# Custom_Arduino.net
KiCad netlist of a schematic drawn in Altium Designer
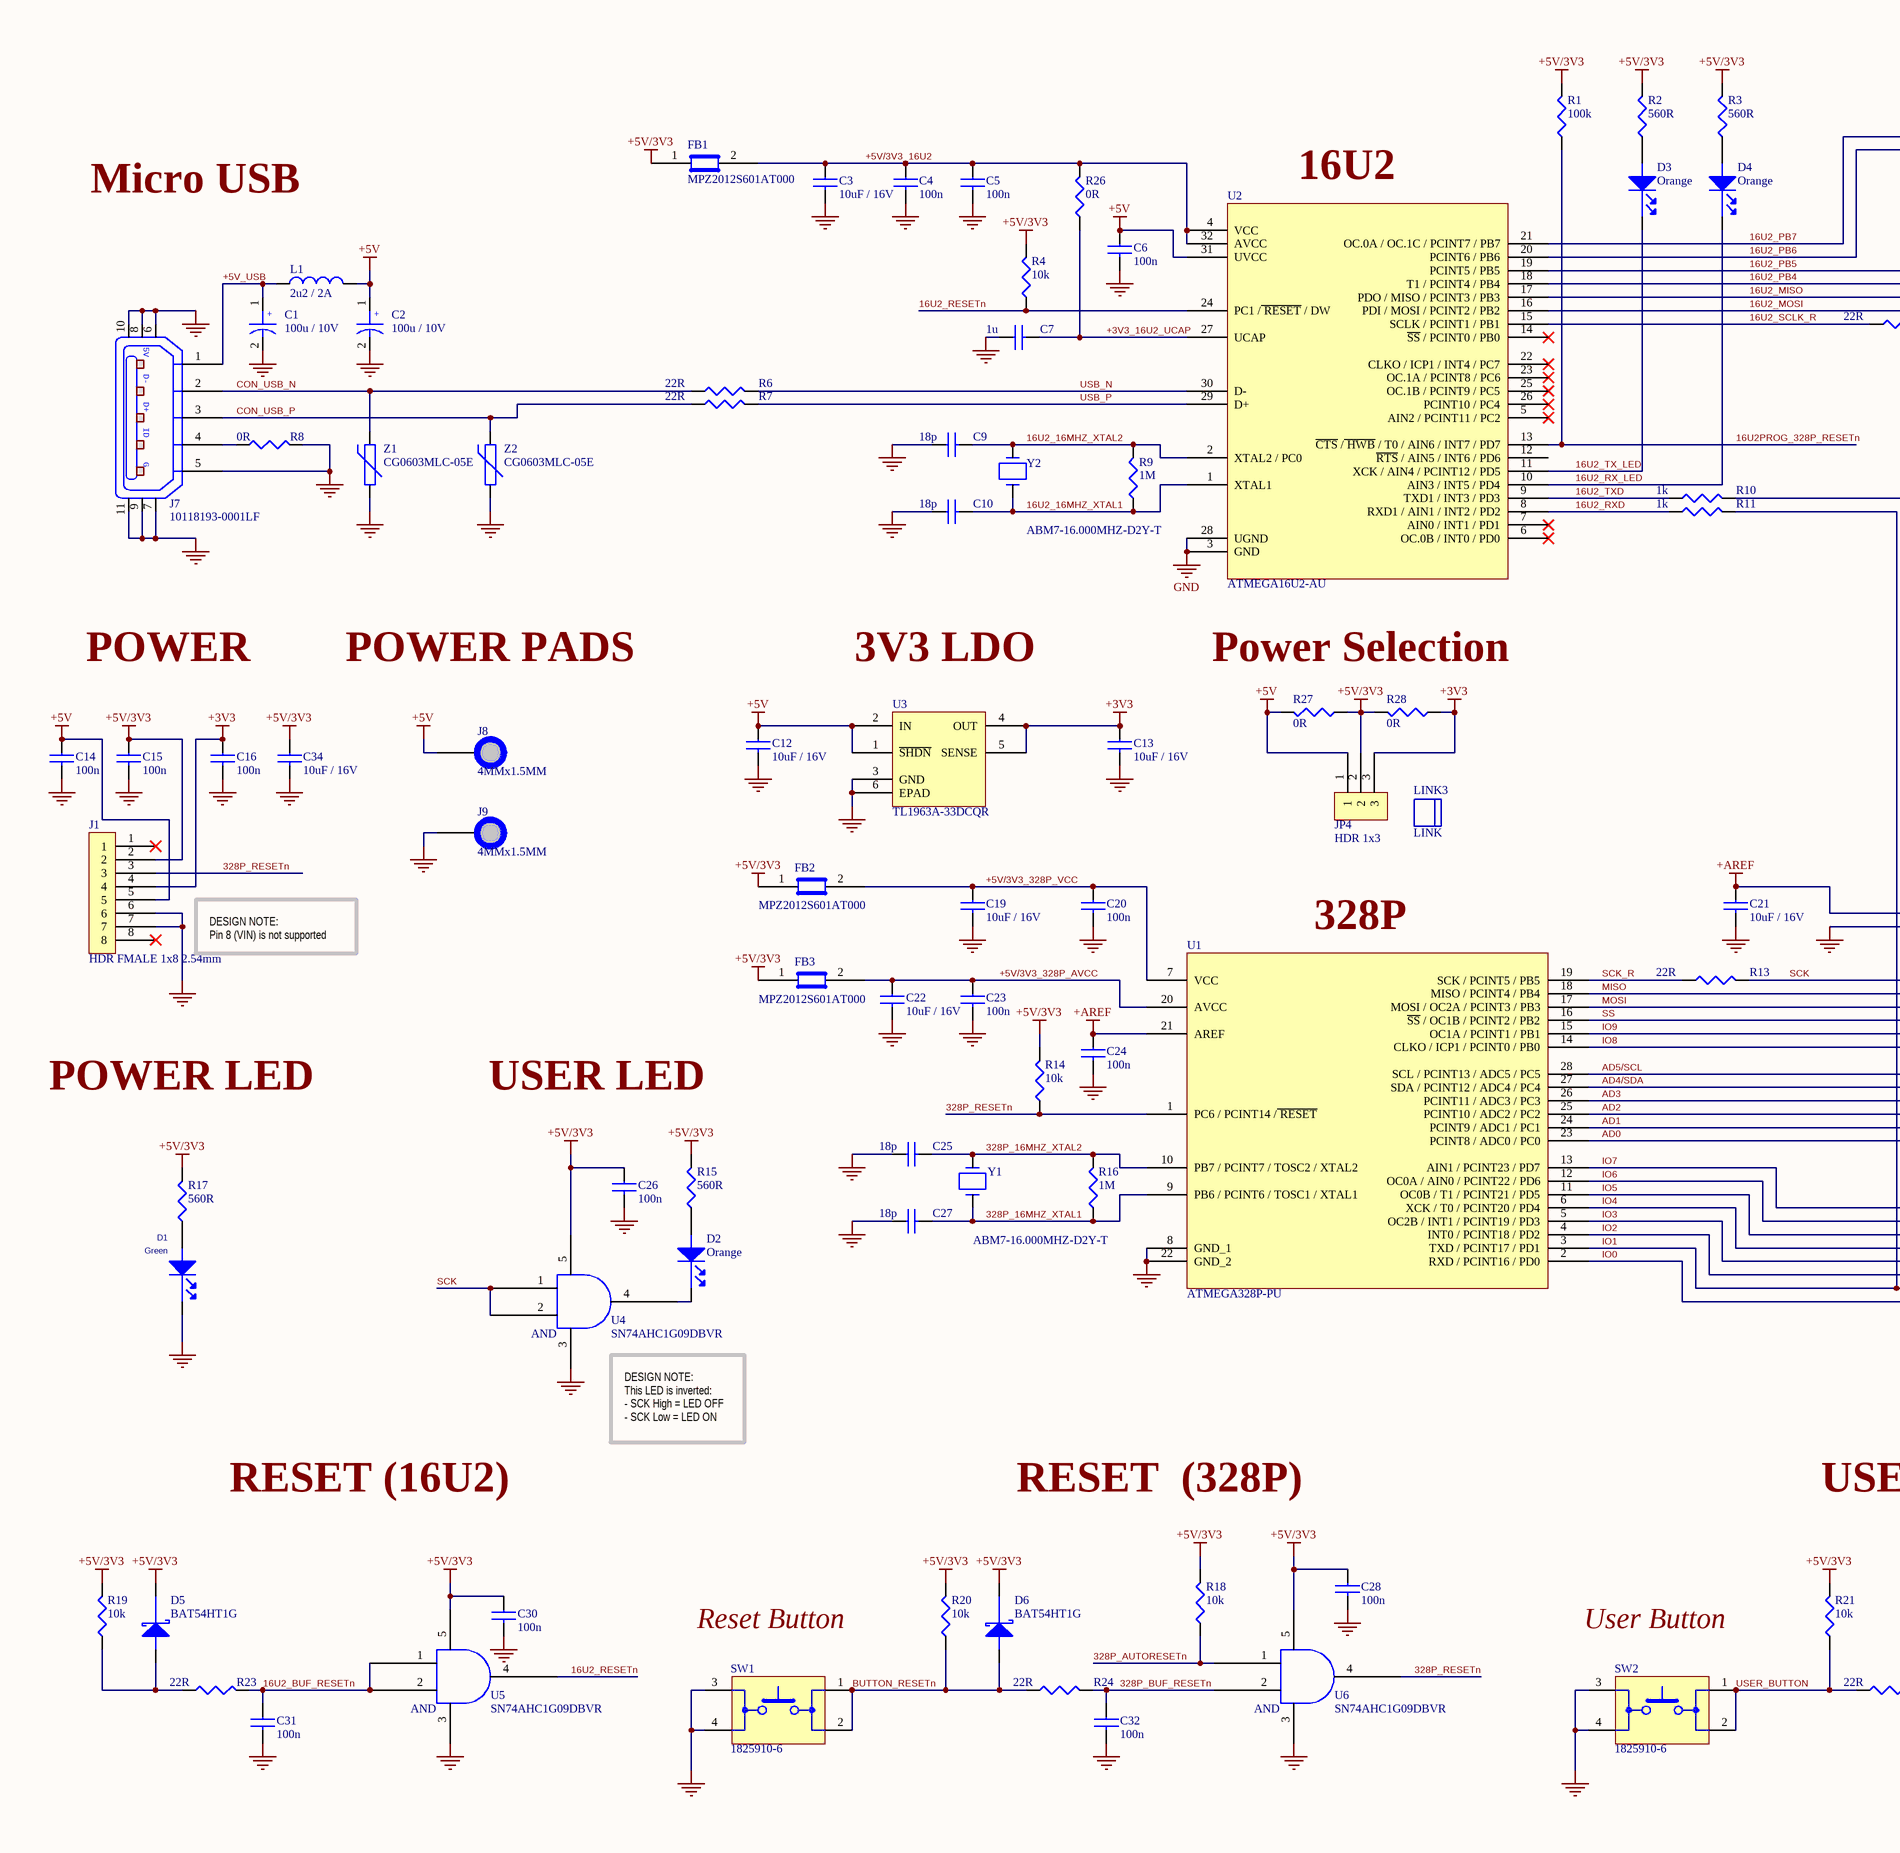
[diagram p0: Custom_Arduino.SchDoc, left]
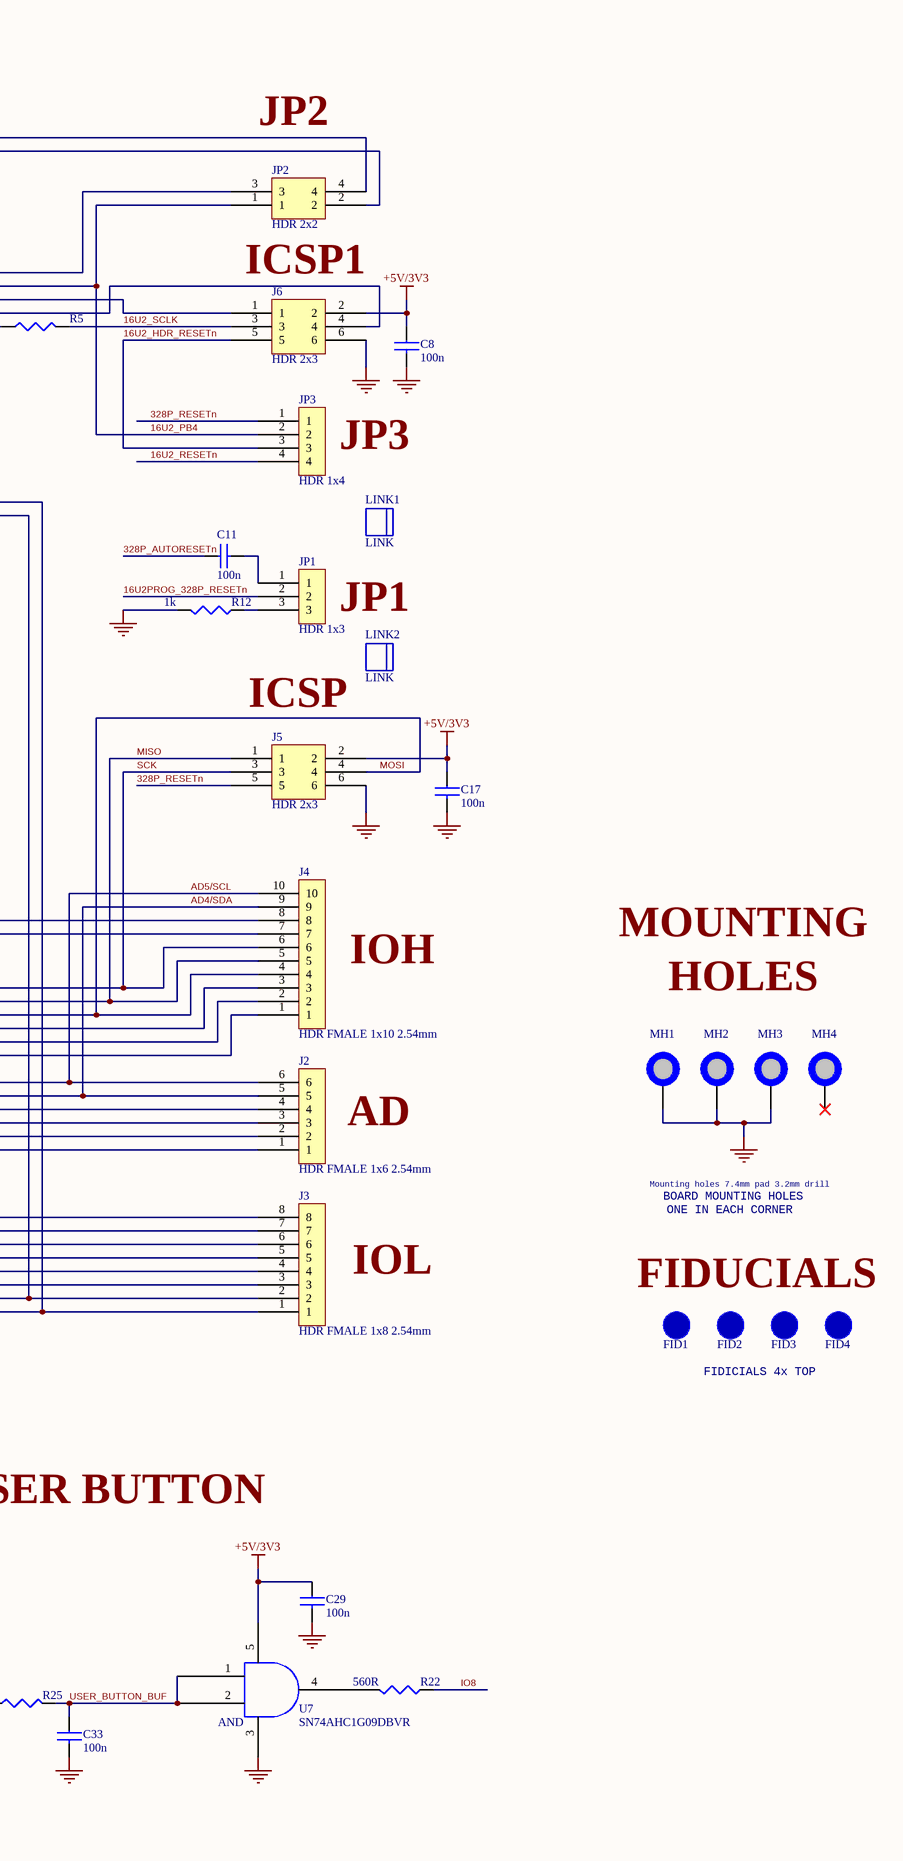
[diagram p1: Custom_Arduino.SchDoc, right]

(export (version "E")
  (design (tool "Eeschema 10.0.6"))
  (components
    (comp (ref "C1")
      (value "100u / 10V")
      (footprint "C_ALU_C_SIZE")
      (description "CAP ALUM 100UF 10V 20% SMD")
      (fields
        (field (name "MANUFACTURER") "Panasonic Electronic Components")
        (field (name "MANUFACTURER PART NUMBER") "EEE-1AA101WR")
        (field (name ".CREATOR") "MM")
        (field (name ".CHECKED PCB") "RF")
        (field (name ".CHECKED SCH") "RF")
      )
      (libsource (lib "My_lib") (part "EEE-1AA101WR"))
    )
    (comp (ref "C2")
      (value "100u / 10V")
      (footprint "C_ALU_C_SIZE")
      (description "CAP ALUM 100UF 10V 20% SMD")
      (fields
        (field (name "MANUFACTURER") "Panasonic Electronic Components")
        (field (name "MANUFACTURER PART NUMBER") "EEE-1AA101WR")
        (field (name ".CREATOR") "MM")
        (field (name ".CHECKED PCB") "RF")
        (field (name ".CHECKED SCH") "RF")
      )
      (libsource (lib "My_lib") (part "EEE-1AA101WR"))
    )
    (comp (ref "C3")
      (value "10uF / 16V")
      (footprint "C0805")
      (description "CAP CER 10UF 16V 20% X5R 0805")
      (fields
        (field (name "MANUFACTURER") "TDK Corporation")
        (field (name "MANUFACTURER PART NUMBER") "C2012X5R1C106M/1.25")
      )
      (libsource (lib "My_lib") (part "C2012X5R1C106M"))
    )
    (comp (ref "C4")
      (value "100n")
      (footprint "C0805")
      (description "CAP CER 0.1UF 50V 10% X7R 0805")
      (fields
        (field (name "MANUFACTURER") "TDK Corporation")
        (field (name "MANUFACTURER PART NUMBER") "C2012X7R1H104K085AA")
        (field (name ".CREATOR") "MM")
        (field (name ".CHECKED PCB") "RF")
        (field (name ".CHECKED SCH") "RF")
      )
      (libsource (lib "My_lib") (part "C2012X7R1H104K085AA"))
    )
    (comp (ref "C5")
      (value "100n")
      (footprint "C0805")
      (description "CAP CER 0.1UF 50V 10% X7R 0805")
      (fields
        (field (name "MANUFACTURER") "TDK Corporation")
        (field (name "MANUFACTURER PART NUMBER") "C2012X7R1H104K085AA")
        (field (name ".CREATOR") "MM")
        (field (name ".CHECKED PCB") "RF")
        (field (name ".CHECKED SCH") "RF")
      )
      (libsource (lib "My_lib") (part "C2012X7R1H104K085AA"))
    )
    (comp (ref "C6")
      (value "100n")
      (footprint "C0805")
      (description "CAP CER 0.1UF 50V 10% X7R 0805")
      (fields
        (field (name "MANUFACTURER") "TDK Corporation")
        (field (name "MANUFACTURER PART NUMBER") "C2012X7R1H104K085AA")
        (field (name ".CREATOR") "MM")
        (field (name ".CHECKED PCB") "RF")
        (field (name ".CHECKED SCH") "RF")
      )
      (libsource (lib "My_lib") (part "C2012X7R1H104K085AA"))
    )
    (comp (ref "C7")
      (value "1u")
      (footprint "C0805")
      (description "CAP CER 1UF 25V 10% X5R 0805")
      (fields
        (field (name "MANUFACTURER") "TDK Corporation")
        (field (name "MANUFACTURER PART NUMBER") "C2012X5R1E105K125AA")
        (field (name ".CREATOR") "MM")
        (field (name ".CHECKED PCB") "RF")
        (field (name ".CHECKED SCH") "RF")
      )
      (libsource (lib "My_lib") (part "C2012X5R1E105K125AA"))
    )
    (comp (ref "C8")
      (value "100n")
      (footprint "C0805")
      (description "CAP CER 0.1UF 50V 10% X7R 0805")
      (fields
        (field (name "MANUFACTURER") "TDK Corporation")
        (field (name "MANUFACTURER PART NUMBER") "C2012X7R1H104K085AA")
        (field (name ".CREATOR") "MM")
        (field (name ".CHECKED PCB") "RF")
        (field (name ".CHECKED SCH") "RF")
      )
      (libsource (lib "My_lib") (part "C2012X7R1H104K085AA"))
    )
    (comp (ref "C9")
      (value "18p")
      (footprint "C0805")
      (description "CAP CER 18PF 50V 5% NP0 0805")
      (fields
        (field (name "MANUFACTURER") "Kemet")
        (field (name "MANUFACTURER PART NUMBER") "C0805C180J5GACTU")
        (field (name ".CREATOR") "MM")
        (field (name ".CHECKED PCB") "RF")
        (field (name ".CHECKED SCH") "RF")
      )
      (libsource (lib "My_lib") (part "C0805C180J5GACTU"))
    )
    (comp (ref "C10")
      (value "18p")
      (footprint "C0805")
      (description "CAP CER 18PF 50V 5% NP0 0805")
      (fields
        (field (name "MANUFACTURER") "Kemet")
        (field (name "MANUFACTURER PART NUMBER") "C0805C180J5GACTU")
        (field (name ".CREATOR") "MM")
        (field (name ".CHECKED PCB") "RF")
        (field (name ".CHECKED SCH") "RF")
      )
      (libsource (lib "My_lib") (part "C0805C180J5GACTU"))
    )
    (comp (ref "C11")
      (value "100n")
      (footprint "C0805")
      (description "CAP CER 0.1UF 50V 10% X7R 0805")
      (fields
        (field (name "MANUFACTURER") "TDK Corporation")
        (field (name "MANUFACTURER PART NUMBER") "C2012X7R1H104K085AA")
        (field (name ".CREATOR") "MM")
        (field (name ".CHECKED PCB") "RF")
        (field (name ".CHECKED SCH") "RF")
      )
      (libsource (lib "My_lib") (part "C2012X7R1H104K085AA"))
    )
    (comp (ref "C12")
      (value "10uF / 16V")
      (footprint "C0805")
      (description "CAP CER 10UF 16V 20% X5R 0805")
      (fields
        (field (name "MANUFACTURER") "TDK Corporation")
        (field (name "MANUFACTURER PART NUMBER") "C2012X5R1C106M/1.25")
      )
      (libsource (lib "My_lib") (part "C2012X5R1C106M"))
    )
    (comp (ref "C13")
      (value "10uF / 16V")
      (footprint "C0805")
      (description "CAP CER 10UF 16V 20% X5R 0805")
      (fields
        (field (name "MANUFACTURER") "TDK Corporation")
        (field (name "MANUFACTURER PART NUMBER") "C2012X5R1C106M/1.25")
      )
      (libsource (lib "My_lib") (part "C2012X5R1C106M"))
    )
    (comp (ref "C14")
      (value "100n")
      (footprint "C0805")
      (description "CAP CER 0.1UF 50V 10% X7R 0805")
      (fields
        (field (name "MANUFACTURER") "TDK Corporation")
        (field (name "MANUFACTURER PART NUMBER") "C2012X7R1H104K085AA")
        (field (name ".CREATOR") "MM")
        (field (name ".CHECKED PCB") "RF")
        (field (name ".CHECKED SCH") "RF")
      )
      (libsource (lib "My_lib") (part "C2012X7R1H104K085AA"))
    )
    (comp (ref "C15")
      (value "100n")
      (footprint "C0805")
      (description "CAP CER 0.1UF 50V 10% X7R 0805")
      (fields
        (field (name "MANUFACTURER") "TDK Corporation")
        (field (name "MANUFACTURER PART NUMBER") "C2012X7R1H104K085AA")
        (field (name ".CREATOR") "MM")
        (field (name ".CHECKED PCB") "RF")
        (field (name ".CHECKED SCH") "RF")
      )
      (libsource (lib "My_lib") (part "C2012X7R1H104K085AA"))
    )
    (comp (ref "C16")
      (value "100n")
      (footprint "C0805")
      (description "CAP CER 0.1UF 50V 10% X7R 0805")
      (fields
        (field (name "MANUFACTURER") "TDK Corporation")
        (field (name "MANUFACTURER PART NUMBER") "C2012X7R1H104K085AA")
        (field (name ".CREATOR") "MM")
        (field (name ".CHECKED PCB") "RF")
        (field (name ".CHECKED SCH") "RF")
      )
      (libsource (lib "My_lib") (part "C2012X7R1H104K085AA"))
    )
    (comp (ref "C17")
      (value "100n")
      (footprint "C0805")
      (description "CAP CER 0.1UF 50V 10% X7R 0805")
      (fields
        (field (name "MANUFACTURER") "TDK Corporation")
        (field (name "MANUFACTURER PART NUMBER") "C2012X7R1H104K085AA")
        (field (name ".CREATOR") "MM")
        (field (name ".CHECKED PCB") "RF")
        (field (name ".CHECKED SCH") "RF")
      )
      (libsource (lib "My_lib") (part "C2012X7R1H104K085AA"))
    )
    (comp (ref "C19")
      (value "10uF / 16V")
      (footprint "C0805")
      (description "CAP CER 10UF 16V 20% X5R 0805")
      (fields
        (field (name "MANUFACTURER") "TDK Corporation")
        (field (name "MANUFACTURER PART NUMBER") "C2012X5R1C106M/1.25")
      )
      (libsource (lib "My_lib") (part "C2012X5R1C106M"))
    )
    (comp (ref "C20")
      (value "100n")
      (footprint "C0805")
      (description "CAP CER 0.1UF 50V 10% X7R 0805")
      (fields
        (field (name "MANUFACTURER") "TDK Corporation")
        (field (name "MANUFACTURER PART NUMBER") "C2012X7R1H104K085AA")
        (field (name ".CREATOR") "MM")
        (field (name ".CHECKED PCB") "RF")
        (field (name ".CHECKED SCH") "RF")
      )
      (libsource (lib "My_lib") (part "C2012X7R1H104K085AA"))
    )
    (comp (ref "C21")
      (value "10uF / 16V")
      (footprint "C0805")
      (description "CAP CER 10UF 16V 20% X5R 0805")
      (fields
        (field (name "MANUFACTURER") "TDK Corporation")
        (field (name "MANUFACTURER PART NUMBER") "C2012X5R1C106M/1.25")
      )
      (libsource (lib "My_lib") (part "C2012X5R1C106M"))
    )
    (comp (ref "C22")
      (value "10uF / 16V")
      (footprint "C0805")
      (description "CAP CER 10UF 16V 20% X5R 0805")
      (fields
        (field (name "MANUFACTURER") "TDK Corporation")
        (field (name "MANUFACTURER PART NUMBER") "C2012X5R1C106M/1.25")
      )
      (libsource (lib "My_lib") (part "C2012X5R1C106M"))
    )
    (comp (ref "C23")
      (value "100n")
      (footprint "C0805")
      (description "CAP CER 0.1UF 50V 10% X7R 0805")
      (fields
        (field (name "MANUFACTURER") "TDK Corporation")
        (field (name "MANUFACTURER PART NUMBER") "C2012X7R1H104K085AA")
        (field (name ".CREATOR") "MM")
        (field (name ".CHECKED PCB") "RF")
        (field (name ".CHECKED SCH") "RF")
      )
      (libsource (lib "My_lib") (part "C2012X7R1H104K085AA"))
    )
    (comp (ref "C24")
      (value "100n")
      (footprint "C0805")
      (description "CAP CER 0.1UF 50V 10% X7R 0805")
      (fields
        (field (name "MANUFACTURER") "TDK Corporation")
        (field (name "MANUFACTURER PART NUMBER") "C2012X7R1H104K085AA")
        (field (name ".CREATOR") "MM")
        (field (name ".CHECKED PCB") "RF")
        (field (name ".CHECKED SCH") "RF")
      )
      (libsource (lib "My_lib") (part "C2012X7R1H104K085AA"))
    )
    (comp (ref "C25")
      (value "18p")
      (footprint "C0805")
      (description "CAP CER 18PF 50V 5% NP0 0805")
      (fields
        (field (name "MANUFACTURER") "Kemet")
        (field (name "MANUFACTURER PART NUMBER") "C0805C180J5GACTU")
        (field (name ".CREATOR") "MM")
        (field (name ".CHECKED PCB") "RF")
        (field (name ".CHECKED SCH") "RF")
      )
      (libsource (lib "My_lib") (part "C0805C180J5GACTU"))
    )
    (comp (ref "C26")
      (value "100n")
      (footprint "C0805")
      (description "CAP CER 0.1UF 50V 10% X7R 0805")
      (fields
        (field (name "MANUFACTURER") "TDK Corporation")
        (field (name "MANUFACTURER PART NUMBER") "C2012X7R1H104K085AA")
        (field (name ".CREATOR") "MM")
        (field (name ".CHECKED PCB") "RF")
        (field (name ".CHECKED SCH") "RF")
      )
      (libsource (lib "My_lib") (part "C2012X7R1H104K085AA"))
    )
    (comp (ref "C27")
      (value "18p")
      (footprint "C0805")
      (description "CAP CER 18PF 50V 5% NP0 0805")
      (fields
        (field (name "MANUFACTURER") "Kemet")
        (field (name "MANUFACTURER PART NUMBER") "C0805C180J5GACTU")
        (field (name ".CREATOR") "MM")
        (field (name ".CHECKED PCB") "RF")
        (field (name ".CHECKED SCH") "RF")
      )
      (libsource (lib "My_lib") (part "C0805C180J5GACTU"))
    )
    (comp (ref "C28")
      (value "100n")
      (footprint "C0805")
      (description "CAP CER 0.1UF 50V 10% X7R 0805")
      (fields
        (field (name "MANUFACTURER") "TDK Corporation")
        (field (name "MANUFACTURER PART NUMBER") "C2012X7R1H104K085AA")
        (field (name ".CREATOR") "MM")
        (field (name ".CHECKED PCB") "RF")
        (field (name ".CHECKED SCH") "RF")
      )
      (libsource (lib "My_lib") (part "C2012X7R1H104K085AA"))
    )
    (comp (ref "C29")
      (value "100n")
      (footprint "C0805")
      (description "CAP CER 0.1UF 50V 10% X7R 0805")
      (fields
        (field (name "MANUFACTURER") "TDK Corporation")
        (field (name "MANUFACTURER PART NUMBER") "C2012X7R1H104K085AA")
        (field (name ".CREATOR") "MM")
        (field (name ".CHECKED PCB") "RF")
        (field (name ".CHECKED SCH") "RF")
      )
      (libsource (lib "My_lib") (part "C2012X7R1H104K085AA"))
    )
    (comp (ref "C30")
      (value "100n")
      (footprint "C0805")
      (description "CAP CER 0.1UF 50V 10% X7R 0805")
      (fields
        (field (name "MANUFACTURER") "TDK Corporation")
        (field (name "MANUFACTURER PART NUMBER") "C2012X7R1H104K085AA")
        (field (name ".CREATOR") "MM")
        (field (name ".CHECKED PCB") "RF")
        (field (name ".CHECKED SCH") "RF")
      )
      (libsource (lib "My_lib") (part "C2012X7R1H104K085AA"))
    )
    (comp (ref "C31")
      (value "100n")
      (footprint "C0805")
      (description "CAP CER 0.1UF 50V 10% X7R 0805")
      (fields
        (field (name "MANUFACTURER") "TDK Corporation")
        (field (name "MANUFACTURER PART NUMBER") "C2012X7R1H104K085AA")
        (field (name ".CREATOR") "MM")
        (field (name ".CHECKED PCB") "RF")
        (field (name ".CHECKED SCH") "RF")
      )
      (libsource (lib "My_lib") (part "C2012X7R1H104K085AA"))
    )
    (comp (ref "C32")
      (value "100n")
      (footprint "C0805")
      (description "CAP CER 0.1UF 50V 10% X7R 0805")
      (fields
        (field (name "MANUFACTURER") "TDK Corporation")
        (field (name "MANUFACTURER PART NUMBER") "C2012X7R1H104K085AA")
        (field (name ".CREATOR") "MM")
        (field (name ".CHECKED PCB") "RF")
        (field (name ".CHECKED SCH") "RF")
      )
      (libsource (lib "My_lib") (part "C2012X7R1H104K085AA"))
    )
    (comp (ref "C33")
      (value "100n")
      (footprint "C0805")
      (description "CAP CER 0.1UF 50V 10% X7R 0805")
      (fields
        (field (name "MANUFACTURER") "TDK Corporation")
        (field (name "MANUFACTURER PART NUMBER") "C2012X7R1H104K085AA")
        (field (name ".CREATOR") "MM")
        (field (name ".CHECKED PCB") "RF")
        (field (name ".CHECKED SCH") "RF")
      )
      (libsource (lib "My_lib") (part "C2012X7R1H104K085AA"))
    )
    (comp (ref "C34")
      (value "10uF / 16V")
      (footprint "C0805")
      (description "CAP CER 10UF 16V 20% X5R 0805")
      (fields
        (field (name "MANUFACTURER") "TDK Corporation")
        (field (name "MANUFACTURER PART NUMBER") "C2012X5R1C106M/1.25")
      )
      (libsource (lib "My_lib") (part "C2012X5R1C106M"))
    )
    (comp (ref "D1")
      (value "Green")
      (footprint "LED_0603")
      (description "LED SMARTLED GREEN 570NM 0603")
      (fields
        (field (name "MANUFACTURER") "OSRAM Opto Semiconductors Inc")
        (field (name "MANUFACTURER PART NUMBER") "LG L29K-G2J1-24-Z")
      )
      (libsource (lib "My_lib") (part "LG L29K-G2J1-24-Z"))
    )
    (comp (ref "D2")
      (value "Orange")
      (footprint "LED_0603")
      (description "LED SMARTLED ORANGE 606NM 0603")
      (fields
        (field (name "MANUFACTURER") "OSRAM Opto Semiconductors Inc")
        (field (name "MANUFACTURER PART NUMBER") "LO L29K-H2K1-24-Z")
      )
      (libsource (lib "My_lib") (part "LO L29K-H2K1-24-Z"))
    )
    (comp (ref "D3")
      (value "Orange")
      (footprint "LED_0603")
      (description "LED SMARTLED ORANGE 606NM 0603")
      (fields
        (field (name "MANUFACTURER") "OSRAM Opto Semiconductors Inc")
        (field (name "MANUFACTURER PART NUMBER") "LO L29K-H2K1-24-Z")
      )
      (libsource (lib "My_lib") (part "LO L29K-H2K1-24-Z"))
    )
    (comp (ref "D4")
      (value "Orange")
      (footprint "LED_0603")
      (description "LED SMARTLED ORANGE 606NM 0603")
      (fields
        (field (name "MANUFACTURER") "OSRAM Opto Semiconductors Inc")
        (field (name "MANUFACTURER PART NUMBER") "LO L29K-H2K1-24-Z")
      )
      (libsource (lib "My_lib") (part "LO L29K-H2K1-24-Z"))
    )
    (comp (ref "D5")
      (value "BAT54HT1G")
      (footprint "SOD323")
      (description "DIODE SCHOTTKY 30V 0.2A SOD323")
      (fields (field (name "MANUFACTURER") "Fairchild Semiconductor") (field (name ".CREATOR") "MM"))
      (libsource (lib "My_lib") (part "BAT54HT1G"))
    )
    (comp (ref "D6")
      (value "BAT54HT1G")
      (footprint "SOD323")
      (description "DIODE SCHOTTKY 30V 0.2A SOD323")
      (fields (field (name "MANUFACTURER") "Fairchild Semiconductor") (field (name ".CREATOR") "MM"))
      (libsource (lib "My_lib") (part "BAT54HT1G"))
    )
    (comp (ref "FB1")
      (value "MPZ2012S601AT000")
      (footprint "C0805")
      (description "FERRITE CHIP BEAD 600 OHM SMD")
      (fields
        (field (name "MANUFACTURER") "TDK Corporation")
        (field (name ".CREATOR") "MM")
        (field (name ".CHECKED PCB") "RF")
        (field (name ".CHECKED SCH") "RF")
      )
      (libsource (lib "My_lib") (part "MPZ2012S601AT000"))
    )
    (comp (ref "FB2")
      (value "MPZ2012S601AT000")
      (footprint "C0805")
      (description "FERRITE CHIP BEAD 600 OHM SMD")
      (fields
        (field (name "MANUFACTURER") "TDK Corporation")
        (field (name ".CREATOR") "MM")
        (field (name ".CHECKED PCB") "RF")
        (field (name ".CHECKED SCH") "RF")
      )
      (libsource (lib "My_lib") (part "MPZ2012S601AT000"))
    )
    (comp (ref "FB3")
      (value "MPZ2012S601AT000")
      (footprint "C0805")
      (description "FERRITE CHIP BEAD 600 OHM SMD")
      (fields
        (field (name "MANUFACTURER") "TDK Corporation")
        (field (name ".CREATOR") "MM")
        (field (name ".CHECKED PCB") "RF")
        (field (name ".CHECKED SCH") "RF")
      )
      (libsource (lib "My_lib") (part "MPZ2012S601AT000"))
    )
    (comp (ref "FID1")
      (value "FID_1MMC")
      (footprint "FID_40X120D")
      (description "Fiducial 40mil Diameter, 120mil Mask")
      (libsource (lib "My_lib") (part "FID_1MMC"))
    )
    (comp (ref "FID2")
      (value "FID_1MMC")
      (footprint "FID_40X120D")
      (description "Fiducial 40mil Diameter, 120mil Mask")
      (libsource (lib "My_lib") (part "FID_1MMC"))
    )
    (comp (ref "FID3")
      (value "FID_1MMC")
      (footprint "FID_40X120D")
      (description "Fiducial 40mil Diameter, 120mil Mask")
      (libsource (lib "My_lib") (part "FID_1MMC"))
    )
    (comp (ref "FID4")
      (value "FID_1MMC")
      (footprint "FID_40X120D")
      (description "Fiducial 40mil Diameter, 120mil Mask")
      (libsource (lib "My_lib") (part "FID_1MMC"))
    )
    (comp (ref "J1")
      (value "HDR FMALE 1x8 2.54mm")
      (footprint "Hdr_Female_1x8_2.54mm")
      (description "08-WAY SIL VERT SOCKET L/FREE")
      (fields
        (field (name "MANUFACTURER") "Harwin Inc")
        (field (name "MANUFACTURER PART NUMBER") "M20-7820842")
        (field (name ".CREATOR") "MM")
        (field (name ".CHECKED PCB") "RF")
        (field (name ".CHECKED SCH") "RF")
      )
      (libsource (lib "") (part "M20-7820842_1"))
    )
    (comp (ref "J2")
      (value "HDR FMALE 1x6 2.54mm")
      (footprint "Hdr_Female_1x6_2.54mm")
      (description "06-WAY SIL VERT SOCKET L/FREE")
      (fields
        (field (name "MANUFACTURER") "Harwin Inc")
        (field (name "MANUFACTURER PART NUMBER") "M20-7820646")
        (field (name ".CHECKED PCB") "MM")
        (field (name ".CHECKED SCH") "MM")
        (field (name ".CREATOR") "MM")
      )
      (libsource (lib "My_lib") (part "M20-7820646"))
    )
    (comp (ref "J3")
      (value "HDR FMALE 1x8 2.54mm")
      (footprint "Hdr_Female_1x8_2.54mm")
      (description "08-WAY SIL VERT SOCKET L/FREE")
      (fields
        (field (name "MANUFACTURER") "Harwin Inc")
        (field (name "MANUFACTURER PART NUMBER") "M20-7820842")
        (field (name ".CREATOR") "MM")
        (field (name ".CHECKED PCB") "RF")
        (field (name ".CHECKED SCH") "RF")
      )
      (libsource (lib "My_lib") (part "M20-7820842"))
    )
    (comp (ref "J4")
      (value "HDR FMALE 1x10 2.54mm")
      (footprint "Hdr_Female_1x10_2.54mm")
      (description "10-WAY SIL VERT SOCKET L/FREE")
      (fields
        (field (name "MANUFACTURER") "Harwin Inc")
        (field (name "MANUFACTURER PART NUMBER") "M20-7821046")
        (field (name ".CREATOR") "MM")
        (field (name ".CHECKED PCB") "RF")
        (field (name ".CHECKED SCH") "RF")
      )
      (libsource (lib "My_lib") (part "M20-7821046"))
    )
    (comp (ref "J5")
      (value "HDR 2x3")
      (footprint "HDR_2x3_2.54MM")
      (description "CONN HEADER 6POS .100 STR 30AU")
      (fields
        (field (name "MANUFACTURER") "FCI")
        (field (name "MANUFACTURER PART NUMBER") "67997-106HLF")
        (field (name ".CREATOR") "MM")
        (field (name ".CHECKED PCB") "RF")
        (field (name ".CHECKED SCH") "RF")
      )
      (libsource (lib "My_lib") (part "67997-106HLF"))
    )
    (comp (ref "J6")
      (value "HDR 2x3")
      (footprint "HDR_2x3_2.54MM")
      (description "CONN HEADER 6POS .100 STR 30AU")
      (fields
        (field (name "MANUFACTURER") "FCI")
        (field (name "MANUFACTURER PART NUMBER") "67997-106HLF")
        (field (name ".CREATOR") "MM")
        (field (name ".CHECKED PCB") "RF")
        (field (name ".CHECKED SCH") "RF")
      )
      (libsource (lib "My_lib") (part "67997-106HLF"))
    )
    (comp (ref "J7")
      (value "10118193-0001LF")
      (footprint "10118193")
      (description "CONN USB MICRO B RECPT SMT R/A")
      (fields
        (field (name "MANUFACTURER") "FCI")
        (field (name ".CREATOR") "MM")
        (field (name ".CHECKED PCB") "RF")
        (field (name ".CHECKED SCH") "MM")
      )
      (libsource (lib "My_lib") (part "10118193-0001LF"))
    )
    (comp (ref "J8")
      (value "4MMx1.5MM")
      (footprint "PAD_WITH_HOLE_4MMx1.5MM")
      (description "Pad with a hole 4mm x 1.5mm")
      (libsource (lib "My_lib") (part "PAD_WITH_HOLE_4MMx1.5MM"))
    )
    (comp (ref "J9")
      (value "4MMx1.5MM")
      (footprint "PAD_WITH_HOLE_4MMx1.5MM")
      (description "Pad with a hole 4mm x 1.5mm")
      (libsource (lib "My_lib") (part "PAD_WITH_HOLE_4MMx1.5MM"))
    )
    (comp (ref "JP1")
      (value "HDR 1x3")
      (footprint "Hdr_1x3_2.54mm")
      (description "BERGSTIK II .100\" SR STRAIGHT")
      (fields
        (field (name "MANUFACTURER") "FCI")
        (field (name "MANUFACTURER PART NUMBER") "68000-103HLF")
        (field (name ".CREATOR") "MM")
      )
      (libsource (lib "") (part "68000-103HLF_1"))
    )
    (comp (ref "JP2")
      (value "HDR 2x2")
      (footprint "HDR_2x2_2.54MM")
      (description "CONN HEADER 4POS .100 STR 15AU")
      (fields
        (field (name "MANUFACTURER") "FCI")
        (field (name "MANUFACTURER PART NUMBER") "68602-204HLF")
        (field (name ".CREATOR") "MM")
        (field (name ".CHECKED PCB") "RF")
        (field (name ".CHECKED SCH") "RF")
      )
      (libsource (lib "My_lib") (part "68602-204HLF"))
    )
    (comp (ref "JP3")
      (value "HDR 1x4")
      (footprint "HDR_1x4_2.54MM")
      (description "CONN HEADER 4POS .100 STR 15AU")
      (fields
        (field (name "MANUFACTURER") "FCI")
        (field (name "MANUFACTURER PART NUMBER") "68001-204HLF")
        (field (name ".CHECKED PCB") "RF")
        (field (name ".CHECKED SCH") "RF")
      )
      (libsource (lib "My_lib") (part "68001-204HLF"))
    )
    (comp (ref "JP4")
      (value "HDR 1x3")
      (footprint "Hdr_1x3_2.54mm")
      (description "BERGSTIK II .100\" SR STRAIGHT")
      (fields
        (field (name "MANUFACTURER") "FCI")
        (field (name "MANUFACTURER PART NUMBER") "68000-103HLF")
        (field (name ".CREATOR") "MM")
      )
      (libsource (lib "My_lib") (part "68000-103HLF"))
    )
    (comp (ref "L1")
      (value "2u2 / 2A")
      (footprint "C1210_IND")
      (description "FIXED IND 2.2UH 2A 80 MOHM SMD")
      (fields
        (field (name "MANUFACTURER") "Kemet")
        (field (name "MANUFACTURER PART NUMBER") "L1210R2R2MDWIT")
        (field (name ".CREATOR") "MM")
        (field (name ".CHECKED PCB") "RF")
        (field (name ".CHECKED SCH") "RF")
      )
      (libsource (lib "My_lib") (part "L1210R2R2MDWIT"))
    )
    (comp (ref "LINK1")
      (value "LINK")
      (description "CONN JUMPER SHORTING .100\" GOLD")
      (fields
        (field (name "MANUFACTURER") "Sullins Connector Solutions")
        (field (name "MANUFACTURER PART NUMBER") "QPC02SXGN-RC")
      )
      (libsource (lib "My_lib") (part "QPC02SXGN-RC"))
    )
    (comp (ref "LINK2")
      (value "LINK")
      (description "CONN JUMPER SHORTING .100\" GOLD")
      (fields
        (field (name "MANUFACTURER") "Sullins Connector Solutions")
        (field (name "MANUFACTURER PART NUMBER") "QPC02SXGN-RC")
      )
      (libsource (lib "My_lib") (part "QPC02SXGN-RC"))
    )
    (comp (ref "LINK3")
      (value "LINK")
      (description "CONN JUMPER SHORTING .100\" GOLD")
      (fields
        (field (name "MANUFACTURER") "Sullins Connector Solutions")
        (field (name "MANUFACTURER PART NUMBER") "QPC02SXGN-RC")
      )
      (libsource (lib "My_lib") (part "QPC02SXGN-RC"))
    )
    (comp (ref "MH1")
      (value "MH_7.4MMC_3.2MMD")
      (footprint "MH_7.4MMD_3.2MMD")
      (description "Mounting Hole 7.4mm Diameter, 3.2mm Drill")
      (fields (field (name ".CREATOR") "MM"))
      (libsource (lib "My_lib") (part "MH_7.4MMC_3.2MMD"))
    )
    (comp (ref "MH2")
      (value "MH_7.4MMC_3.2MMD")
      (footprint "MH_7.4MMD_3.2MMD")
      (description "Mounting Hole 7.4mm Diameter, 3.2mm Drill")
      (fields (field (name ".CREATOR") "MM"))
      (libsource (lib "My_lib") (part "MH_7.4MMC_3.2MMD"))
    )
    (comp (ref "MH3")
      (value "MH_7.4MMC_3.2MMD")
      (footprint "MH_7.4MMD_3.2MMD")
      (description "Mounting Hole 7.4mm Diameter, 3.2mm Drill")
      (fields (field (name ".CREATOR") "MM"))
      (libsource (lib "My_lib") (part "MH_7.4MMC_3.2MMD"))
    )
    (comp (ref "MH4")
      (value "MH_7.4MMNC_3.2MMD")
      (footprint "MH_7.4MMD_3.2MMD_NON_COPPER_NPTH")
      (description "Mounting Hole 7.4mm Diameter (Non Copper), 3.2mm Drill NPTH")
      (libsource (lib "My_lib") (part "MH_7.4MMNC_3.2MMD"))
    )
    (comp (ref "R1")
      (value "100k")
      (footprint "R0805")
      (description "RES SMD 100K OHM 1% 1/8W 0805")
      (fields
        (field (name "MANUFACTURER") "Yageo")
        (field (name "MANUFACTURER PART NUMBER") "RC0805FR-07100KL")
        (field (name ".CREATOR") "MM")
        (field (name ".CHECKED PCB") "RF")
        (field (name ".CHECKED SCH") "RF")
      )
      (libsource (lib "My_lib") (part "RC0805FR-07100KL"))
    )
    (comp (ref "R2")
      (value "560R")
      (footprint "R0805")
      (description "RES SMD 560 OHM 1% 1/8W 0805")
      (fields
        (field (name "MANUFACTURER") "Yageo")
        (field (name "MANUFACTURER PART NUMBER") "RC0805FR-07560RL")
        (field (name ".CREATOR") "MM")
        (field (name ".CHECKED PCB") "RF")
        (field (name ".CHECKED SCH") "RF")
      )
      (libsource (lib "My_lib") (part "RC0805FR-07560RL"))
    )
    (comp (ref "R3")
      (value "560R")
      (footprint "R0805")
      (description "RES SMD 560 OHM 1% 1/8W 0805")
      (fields
        (field (name "MANUFACTURER") "Yageo")
        (field (name "MANUFACTURER PART NUMBER") "RC0805FR-07560RL")
        (field (name ".CREATOR") "MM")
        (field (name ".CHECKED PCB") "RF")
        (field (name ".CHECKED SCH") "RF")
      )
      (libsource (lib "My_lib") (part "RC0805FR-07560RL"))
    )
    (comp (ref "R4")
      (value "10k")
      (footprint "R0805")
      (description "RES SMD 10K OHM 1% 1/8W 0805")
      (fields
        (field (name "MANUFACTURER") "Yageo")
        (field (name "MANUFACTURER PART NUMBER") "RC0805FR-0710KL")
        (field (name ".CREATOR") "MM")
        (field (name ".CHECKED PCB") "RF")
        (field (name ".CHECKED SCH") "RF")
      )
      (libsource (lib "My_lib") (part "RC0805FR-0710KL"))
    )
    (comp (ref "R5")
      (value "22R")
      (footprint "R0805")
      (description "RES SMD 22 OHM 1% 1/8W 0805")
      (fields
        (field (name "MANUFACTURER") "Yageo")
        (field (name "MANUFACTURER PART NUMBER") "RC0805FR-0722RL")
        (field (name ".CREATOR") "MM")
        (field (name ".CHECKED PCB") "RF")
        (field (name ".CHECKED SCH") "RF")
      )
      (libsource (lib "My_lib") (part "RC0805FR-0722RL"))
    )
    (comp (ref "R6")
      (value "22R")
      (footprint "R0805")
      (description "RES SMD 22 OHM 1% 1/8W 0805")
      (fields
        (field (name "MANUFACTURER") "Yageo")
        (field (name "MANUFACTURER PART NUMBER") "RC0805FR-0722RL")
        (field (name ".CREATOR") "MM")
        (field (name ".CHECKED PCB") "RF")
        (field (name ".CHECKED SCH") "RF")
      )
      (libsource (lib "My_lib") (part "RC0805FR-0722RL"))
    )
    (comp (ref "R7")
      (value "22R")
      (footprint "R0805")
      (description "RES SMD 22 OHM 1% 1/8W 0805")
      (fields
        (field (name "MANUFACTURER") "Yageo")
        (field (name "MANUFACTURER PART NUMBER") "RC0805FR-0722RL")
        (field (name ".CREATOR") "MM")
        (field (name ".CHECKED PCB") "RF")
        (field (name ".CHECKED SCH") "RF")
      )
      (libsource (lib "My_lib") (part "RC0805FR-0722RL"))
    )
    (comp (ref "R8")
      (value "0R")
      (footprint "R0805")
      (description "RES 0.0 OHM 1/8W 0805 SMD")
      (fields
        (field (name "MANUFACTURER") "Yageo")
        (field (name "MANUFACTURER PART NUMBER") "RC0805JR-070RL")
        (field (name ".CHECKED PCB") "RF")
        (field (name ".CHECKED SCH") "RF")
      )
      (libsource (lib "My_lib") (part "RC0805JR-070RL"))
    )
    (comp (ref "R9")
      (value "1M")
      (footprint "R0805")
      (description "RES SMD 1M OHM 1% 1/8W 0805")
      (fields
        (field (name "MANUFACTURER") "Yageo")
        (field (name "MANUFACTURER PART NUMBER") "RC0805FR-071ML")
        (field (name ".CREATOR") "MM")
        (field (name ".CHECKED PCB") "RF")
        (field (name ".CHECKED SCH") "RF")
      )
      (libsource (lib "My_lib") (part "RC0805FR-071ML"))
    )
    (comp (ref "R10")
      (value "1k")
      (footprint "R0805")
      (description "RES SMD 1K OHM 1% 1/8W 0805")
      (fields
        (field (name "MANUFACTURER") "Yageo")
        (field (name "MANUFACTURER PART NUMBER") "RC0805FR-071KL")
        (field (name ".CREATOR") "MM")
        (field (name ".CHECKED PCB") "RF")
        (field (name ".CHECKED SCH") "RF")
      )
      (libsource (lib "My_lib") (part "RC0805FR-071KL"))
    )
    (comp (ref "R11")
      (value "1k")
      (footprint "R0805")
      (description "RES SMD 1K OHM 1% 1/8W 0805")
      (fields
        (field (name "MANUFACTURER") "Yageo")
        (field (name "MANUFACTURER PART NUMBER") "RC0805FR-071KL")
        (field (name ".CREATOR") "MM")
        (field (name ".CHECKED PCB") "RF")
        (field (name ".CHECKED SCH") "RF")
      )
      (libsource (lib "My_lib") (part "RC0805FR-071KL"))
    )
    (comp (ref "R12")
      (value "1k")
      (footprint "R0805")
      (description "RES SMD 1K OHM 1% 1/8W 0805")
      (fields
        (field (name "MANUFACTURER") "Yageo")
        (field (name "MANUFACTURER PART NUMBER") "RC0805FR-071KL")
        (field (name ".CREATOR") "MM")
        (field (name ".CHECKED PCB") "RF")
        (field (name ".CHECKED SCH") "RF")
      )
      (libsource (lib "My_lib") (part "RC0805FR-071KL"))
    )
    (comp (ref "R13")
      (value "22R")
      (footprint "R0805")
      (description "RES SMD 22 OHM 1% 1/8W 0805")
      (fields
        (field (name "MANUFACTURER") "Yageo")
        (field (name "MANUFACTURER PART NUMBER") "RC0805FR-0722RL")
        (field (name ".CREATOR") "MM")
        (field (name ".CHECKED PCB") "RF")
        (field (name ".CHECKED SCH") "RF")
      )
      (libsource (lib "My_lib") (part "RC0805FR-0722RL"))
    )
    (comp (ref "R14")
      (value "10k")
      (footprint "R0805")
      (description "RES SMD 10K OHM 1% 1/8W 0805")
      (fields
        (field (name "MANUFACTURER") "Yageo")
        (field (name "MANUFACTURER PART NUMBER") "RC0805FR-0710KL")
        (field (name ".CREATOR") "MM")
        (field (name ".CHECKED PCB") "RF")
        (field (name ".CHECKED SCH") "RF")
      )
      (libsource (lib "My_lib") (part "RC0805FR-0710KL"))
    )
    (comp (ref "R15")
      (value "560R")
      (footprint "R0805")
      (description "RES SMD 560 OHM 1% 1/8W 0805")
      (fields
        (field (name "MANUFACTURER") "Yageo")
        (field (name "MANUFACTURER PART NUMBER") "RC0805FR-07560RL")
        (field (name ".CREATOR") "MM")
        (field (name ".CHECKED PCB") "RF")
        (field (name ".CHECKED SCH") "RF")
      )
      (libsource (lib "My_lib") (part "RC0805FR-07560RL"))
    )
    (comp (ref "R16")
      (value "1M")
      (footprint "R0805")
      (description "RES SMD 1M OHM 1% 1/8W 0805")
      (fields
        (field (name "MANUFACTURER") "Yageo")
        (field (name "MANUFACTURER PART NUMBER") "RC0805FR-071ML")
        (field (name ".CREATOR") "MM")
        (field (name ".CHECKED PCB") "RF")
        (field (name ".CHECKED SCH") "RF")
      )
      (libsource (lib "My_lib") (part "RC0805FR-071ML"))
    )
    (comp (ref "R17")
      (value "560R")
      (footprint "R0805")
      (description "RES SMD 560 OHM 1% 1/8W 0805")
      (fields
        (field (name "MANUFACTURER") "Yageo")
        (field (name "MANUFACTURER PART NUMBER") "RC0805FR-07560RL")
        (field (name ".CREATOR") "MM")
        (field (name ".CHECKED PCB") "RF")
        (field (name ".CHECKED SCH") "RF")
      )
      (libsource (lib "My_lib") (part "RC0805FR-07560RL"))
    )
    (comp (ref "R18")
      (value "10k")
      (footprint "R0805")
      (description "RES SMD 10K OHM 1% 1/8W 0805")
      (fields
        (field (name "MANUFACTURER") "Yageo")
        (field (name "MANUFACTURER PART NUMBER") "RC0805FR-0710KL")
        (field (name ".CREATOR") "MM")
        (field (name ".CHECKED PCB") "RF")
        (field (name ".CHECKED SCH") "RF")
      )
      (libsource (lib "My_lib") (part "RC0805FR-0710KL"))
    )
    (comp (ref "R19")
      (value "10k")
      (footprint "R0805")
      (description "RES SMD 10K OHM 1% 1/8W 0805")
      (fields
        (field (name "MANUFACTURER") "Yageo")
        (field (name "MANUFACTURER PART NUMBER") "RC0805FR-0710KL")
        (field (name ".CREATOR") "MM")
        (field (name ".CHECKED PCB") "RF")
        (field (name ".CHECKED SCH") "RF")
      )
      (libsource (lib "My_lib") (part "RC0805FR-0710KL"))
    )
    (comp (ref "R20")
      (value "10k")
      (footprint "R0805")
      (description "RES SMD 10K OHM 1% 1/8W 0805")
      (fields
        (field (name "MANUFACTURER") "Yageo")
        (field (name "MANUFACTURER PART NUMBER") "RC0805FR-0710KL")
        (field (name ".CREATOR") "MM")
        (field (name ".CHECKED PCB") "RF")
        (field (name ".CHECKED SCH") "RF")
      )
      (libsource (lib "My_lib") (part "RC0805FR-0710KL"))
    )
    (comp (ref "R21")
      (value "10k")
      (footprint "R0805")
      (description "RES SMD 10K OHM 1% 1/8W 0805")
      (fields
        (field (name "MANUFACTURER") "Yageo")
        (field (name "MANUFACTURER PART NUMBER") "RC0805FR-0710KL")
        (field (name ".CREATOR") "MM")
        (field (name ".CHECKED PCB") "RF")
        (field (name ".CHECKED SCH") "RF")
      )
      (libsource (lib "My_lib") (part "RC0805FR-0710KL"))
    )
    (comp (ref "R22")
      (value "560R")
      (footprint "R0805")
      (description "RES SMD 560 OHM 1% 1/8W 0805")
      (fields
        (field (name "MANUFACTURER") "Yageo")
        (field (name "MANUFACTURER PART NUMBER") "RC0805FR-07560RL")
        (field (name ".CREATOR") "MM")
        (field (name ".CHECKED PCB") "RF")
        (field (name ".CHECKED SCH") "RF")
      )
      (libsource (lib "My_lib") (part "RC0805FR-07560RL"))
    )
    (comp (ref "R23")
      (value "22R")
      (footprint "R0805")
      (description "RES SMD 22 OHM 1% 1/8W 0805")
      (fields
        (field (name "MANUFACTURER") "Yageo")
        (field (name "MANUFACTURER PART NUMBER") "RC0805FR-0722RL")
        (field (name ".CREATOR") "MM")
        (field (name ".CHECKED PCB") "RF")
        (field (name ".CHECKED SCH") "RF")
      )
      (libsource (lib "My_lib") (part "RC0805FR-0722RL"))
    )
    (comp (ref "R24")
      (value "22R")
      (footprint "R0805")
      (description "RES SMD 22 OHM 1% 1/8W 0805")
      (fields
        (field (name "MANUFACTURER") "Yageo")
        (field (name "MANUFACTURER PART NUMBER") "RC0805FR-0722RL")
        (field (name ".CREATOR") "MM")
        (field (name ".CHECKED PCB") "RF")
        (field (name ".CHECKED SCH") "RF")
      )
      (libsource (lib "My_lib") (part "RC0805FR-0722RL"))
    )
    (comp (ref "R25")
      (value "22R")
      (footprint "R0805")
      (description "RES SMD 22 OHM 1% 1/8W 0805")
      (fields
        (field (name "MANUFACTURER") "Yageo")
        (field (name "MANUFACTURER PART NUMBER") "RC0805FR-0722RL")
        (field (name ".CREATOR") "MM")
        (field (name ".CHECKED PCB") "RF")
        (field (name ".CHECKED SCH") "RF")
      )
      (libsource (lib "My_lib") (part "RC0805FR-0722RL"))
    )
    (comp (ref "R26")
      (value "0R")
      (footprint "R0805")
      (description "RES 0.0 OHM 1/8W 0805 SMD")
      (fields
        (field (name "MANUFACTURER") "Yageo")
        (field (name "MANUFACTURER PART NUMBER") "RC0805JR-070RL")
        (field (name ".CHECKED PCB") "RF")
        (field (name ".CHECKED SCH") "RF")
      )
      (libsource (lib "My_lib") (part "RC0805JR-070RL"))
    )
    (comp (ref "R27")
      (value "0R")
      (footprint "R0805")
      (description "RES 0.0 OHM 1/8W 0805 SMD")
      (fields
        (field (name "MANUFACTURER") "Yageo")
        (field (name "MANUFACTURER PART NUMBER") "RC0805JR-070RL")
        (field (name ".CHECKED PCB") "RF")
        (field (name ".CHECKED SCH") "RF")
      )
      (libsource (lib "My_lib") (part "RC0805JR-070RL"))
    )
    (comp (ref "R28")
      (value "0R")
      (footprint "R0805")
      (description "RES 0.0 OHM 1/8W 0805 SMD")
      (fields
        (field (name "MANUFACTURER") "Yageo")
        (field (name "MANUFACTURER PART NUMBER") "RC0805JR-070RL")
        (field (name ".CHECKED PCB") "RF")
        (field (name ".CHECKED SCH") "RF")
      )
      (libsource (lib "My_lib") (part "RC0805JR-070RL"))
    )
    (comp (ref "SW1")
      (value "1825910-6")
      (footprint "1825910-6")
      (description "SWITCH TACTILE SPST-NO 0.05A 24V")
      (fields
        (field (name "MANUFACTURER") "TE Connectivity")
        (field (name ".CREATOR") "MM")
        (field (name ".CHECKED PCB") "RF")
        (field (name ".CHECKED SCH") "RF")
      )
      (libsource (lib "My_lib") (part "1825910-6"))
    )
    (comp (ref "SW2")
      (value "1825910-6")
      (footprint "1825910-6")
      (description "SWITCH TACTILE SPST-NO 0.05A 24V")
      (fields
        (field (name "MANUFACTURER") "TE Connectivity")
        (field (name ".CREATOR") "MM")
        (field (name ".CHECKED PCB") "RF")
        (field (name ".CHECKED SCH") "RF")
      )
      (libsource (lib "My_lib") (part "1825910-6"))
    )
    (comp (ref "U1")
      (value "ATMEGA328P-PU")
      (footprint "28_DIP_7.62mm")
      (description "IC MCU 8BIT 32KB FLASH 28DIP")
      (fields
        (field (name "MANUFACTURER") "Atmel")
        (field (name ".CREATOR") "MM")
        (field (name ".CHECKED PCB") "RF")
        (field (name ".CHECKED SCH") "RF")
      )
      (libsource (lib "My_lib") (part "ATMEGA328P-PU"))
    )
    (comp (ref "U2")
      (value "ATMEGA16U2-AU")
      (footprint "TQFP32")
      (description "IC MCU 8BIT 16KB FLASH 32TQFP")
      (fields
        (field (name "MANUFACTURER") "Atmel")
        (field (name ".CREATOR") "MM")
        (field (name ".CHECKED PCB") "RF")
        (field (name ".CHECKED SCH") "RF")
      )
      (libsource (lib "My_lib") (part "ATMEGA16U2-AU"))
    )
    (comp (ref "U3")
      (value "TL1963A-33DCQR")
      (footprint "DCQ (R-PDSO-G6)")
      (description "IC REG LDO 3.3V 1.5A SOT223-6")
      (fields
        (field (name "MANUFACTURER") "Texas Instruments")
        (field (name ".CREATOR") "MM")
        (field (name ".CHECKED PCB") "RF")
        (field (name ".CHECKED SCH") "RF")
      )
      (libsource (lib "My_lib") (part "TL1963A-33DCQR"))
    )
    (comp (ref "U4")
      (value "SN74AHC1G09DBVR")
      (footprint "DBV_SOT_23_5")
      (description "IC GATE AND SGL 2INP SOT23-5")
      (fields (field (name "MANUFACTURER") "Texas Instruments") (field (name ".CREATOR") "MM"))
      (libsource (lib "My_lib") (part "SN74AHC1G09DBVR"))
    )
    (comp (ref "U5")
      (value "SN74AHC1G09DBVR")
      (footprint "DBV_SOT_23_5")
      (description "IC GATE AND SGL 2INP SOT23-5")
      (fields (field (name "MANUFACTURER") "Texas Instruments") (field (name ".CREATOR") "MM"))
      (libsource (lib "My_lib") (part "SN74AHC1G09DBVR"))
    )
    (comp (ref "U6")
      (value "SN74AHC1G09DBVR")
      (footprint "DBV_SOT_23_5")
      (description "IC GATE AND SGL 2INP SOT23-5")
      (fields (field (name "MANUFACTURER") "Texas Instruments") (field (name ".CREATOR") "MM"))
      (libsource (lib "My_lib") (part "SN74AHC1G09DBVR"))
    )
    (comp (ref "U7")
      (value "SN74AHC1G09DBVR")
      (footprint "DBV_SOT_23_5")
      (description "IC GATE AND SGL 2INP SOT23-5")
      (fields (field (name "MANUFACTURER") "Texas Instruments") (field (name ".CREATOR") "MM"))
      (libsource (lib "My_lib") (part "SN74AHC1G09DBVR"))
    )
    (comp (ref "Y1")
      (value "ABM7-16.000MHZ-D2Y-T")
      (footprint "ABM7_v1_1_BIG")
      (description "CRYSTAL 16MHZ 18PF SMD")
      (fields
        (field (name "MANUFACTURER") "Abracon LLC")
        (field (name ".CREATOR") "MM")
        (field (name ".CHECKED PCB") "RF")
        (field (name ".CHECKED SCH") "RF")
      )
      (libsource (lib "My_lib") (part "ABM7-16.000MHZ-D2Y-T"))
    )
    (comp (ref "Y2")
      (value "ABM7-16.000MHZ-D2Y-T")
      (footprint "ABM7_v1_1_BIG")
      (description "CRYSTAL 16MHZ 18PF SMD")
      (fields
        (field (name "MANUFACTURER") "Abracon LLC")
        (field (name ".CREATOR") "MM")
        (field (name ".CHECKED PCB") "RF")
        (field (name ".CHECKED SCH") "RF")
      )
      (libsource (lib "My_lib") (part "ABM7-16.000MHZ-D2Y-T"))
    )
    (comp (ref "Z1")
      (value "CG0603MLC-05E")
      (footprint "R0603")
      (description "VARISTOR 0603")
      (fields
        (field (name "MANUFACTURER") "Bourns Inc.")
        (field (name ".CREATOR") "MM")
        (field (name ".CHECKED PCB") "RF")
        (field (name ".CHECKED SCH") "RF")
      )
      (libsource (lib "My_lib") (part "CG0603MLC-05E"))
    )
    (comp (ref "Z2")
      (value "CG0603MLC-05E")
      (footprint "R0603")
      (description "VARISTOR 0603")
      (fields
        (field (name "MANUFACTURER") "Bourns Inc.")
        (field (name ".CREATOR") "MM")
        (field (name ".CHECKED PCB") "RF")
        (field (name ".CHECKED SCH") "RF")
      )
      (libsource (lib "My_lib") (part "CG0603MLC-05E"))
    )
  )
  (nets
    (net (code "1") (name "+3V3") (class "Default")
      (node (ref "C13") (pin "1") (pinfunction "1_1") (pintype "passive"))
      (node (ref "C16") (pin "1") (pinfunction "1_1") (pintype "passive"))
      (node (ref "J1") (pin "4") (pinfunction "4_4") (pintype "passive"))
      (node (ref "JP4") (pin "3") (pinfunction "3_3") (pintype "passive"))
      (node (ref "R28") (pin "1") (pinfunction "1_1") (pintype "passive"))
      (node (ref "U3") (pin "4") (pinfunction "OUT_4") (pintype "passive"))
      (node (ref "U3") (pin "5") (pinfunction "SENSE_5") (pintype "passive"))
    )
    (net (code "2") (name "+5V") (class "Default")
      (node (ref "C12") (pin "1") (pinfunction "1_1") (pintype "passive"))
      (node (ref "C14") (pin "1") (pinfunction "1_1") (pintype "passive"))
      (node (ref "C2") (pin "1") (pinfunction "1_1") (pintype "passive"))
      (node (ref "C6") (pin "1") (pinfunction "1_1") (pintype "passive"))
      (node (ref "J1") (pin "5") (pinfunction "5_5") (pintype "passive"))
      (node (ref "J8") (pin "1") (pinfunction "1_1") (pintype "passive"))
      (node (ref "JP4") (pin "1") (pinfunction "1_1") (pintype "passive"))
      (node (ref "L1") (pin "2") (pinfunction "2_2") (pintype "passive"))
      (node (ref "R27") (pin "2") (pinfunction "2_2") (pintype "passive"))
      (node (ref "U2") (pin "31") (pinfunction "UVCC_31") (pintype "passive"))
      (node (ref "U3") (pin "1") (pinfunction "~{SHDN}_1") (pintype "passive"))
      (node (ref "U3") (pin "2") (pinfunction "IN_2") (pintype "passive"))
    )
    (net (code "3") (name "+5V{slash}3V3") (class "Default")
      (node (ref "C15") (pin "1") (pinfunction "1_1") (pintype "passive"))
      (node (ref "C17") (pin "1") (pinfunction "1_1") (pintype "passive"))
      (node (ref "C26") (pin "1") (pinfunction "1_1") (pintype "passive"))
      (node (ref "C28") (pin "1") (pinfunction "1_1") (pintype "passive"))
      (node (ref "C29") (pin "1") (pinfunction "1_1") (pintype "passive"))
      (node (ref "C30") (pin "1") (pinfunction "1_1") (pintype "passive"))
      (node (ref "C34") (pin "1") (pinfunction "1_1") (pintype "passive"))
      (node (ref "C8") (pin "1") (pinfunction "1_1") (pintype "passive"))
      (node (ref "D5") (pin "1") (pinfunction "Cathode_1") (pintype "passive"))
      (node (ref "D6") (pin "1") (pinfunction "Cathode_1") (pintype "passive"))
      (node (ref "FB1") (pin "1") (pinfunction "1_1") (pintype "passive"))
      (node (ref "FB2") (pin "1") (pinfunction "1_1") (pintype "passive"))
      (node (ref "FB3") (pin "1") (pinfunction "1_1") (pintype "passive"))
      (node (ref "J1") (pin "2") (pinfunction "2_2") (pintype "passive"))
      (node (ref "J5") (pin "2") (pinfunction "2_2") (pintype "passive"))
      (node (ref "J6") (pin "2") (pinfunction "2_2") (pintype "passive"))
      (node (ref "JP4") (pin "2") (pinfunction "2_2") (pintype "passive"))
      (node (ref "R1") (pin "2") (pinfunction "2_2") (pintype "passive"))
      (node (ref "R14") (pin "2") (pinfunction "2_2") (pintype "passive"))
      (node (ref "R15") (pin "2") (pinfunction "2_2") (pintype "passive"))
      (node (ref "R17") (pin "2") (pinfunction "2_2") (pintype "passive"))
      (node (ref "R18") (pin "2") (pinfunction "2_2") (pintype "passive"))
      (node (ref "R19") (pin "2") (pinfunction "2_2") (pintype "passive"))
      (node (ref "R2") (pin "2") (pinfunction "2_2") (pintype "passive"))
      (node (ref "R20") (pin "2") (pinfunction "2_2") (pintype "passive"))
      (node (ref "R21") (pin "2") (pinfunction "2_2") (pintype "passive"))
      (node (ref "R27") (pin "1") (pinfunction "1_1") (pintype "passive"))
      (node (ref "R28") (pin "2") (pinfunction "2_2") (pintype "passive"))
      (node (ref "R3") (pin "2") (pinfunction "2_2") (pintype "passive"))
      (node (ref "R4") (pin "2") (pinfunction "2_2") (pintype "passive"))
      (node (ref "U4") (pin "5") (pinfunction "VCC_5") (pintype "power_in"))
      (node (ref "U5") (pin "5") (pinfunction "VCC_5") (pintype "power_in"))
      (node (ref "U6") (pin "5") (pinfunction "VCC_5") (pintype "power_in"))
      (node (ref "U7") (pin "5") (pinfunction "VCC_5") (pintype "power_in"))
    )
    (net (code "4") (name "+AREF") (class "Default")
      (node (ref "C21") (pin "1") (pinfunction "1_1") (pintype "passive"))
      (node (ref "C24") (pin "1") (pinfunction "1_1") (pintype "passive"))
      (node (ref "J4") (pin "8") (pinfunction "8_8") (pintype "passive"))
      (node (ref "U1") (pin "21") (pinfunction "AREF_21") (pintype "passive"))
    )
    (net (code "5") (name "/+3V3_16U2_UCAP") (class "Default")
      (node (ref "C7") (pin "2") (pinfunction "2_2") (pintype "passive"))
      (node (ref "R26") (pin "1") (pinfunction "1_1") (pintype "passive"))
      (node (ref "U2") (pin "27") (pinfunction "UCAP_27") (pintype "passive"))
    )
    (net (code "6") (name "/+5V_USB") (class "Default")
      (node (ref "C1") (pin "1") (pinfunction "1_1") (pintype "passive"))
      (node (ref "J7") (pin "1") (pinfunction "P1_1") (pintype "passive"))
      (node (ref "L1") (pin "1") (pinfunction "1_1") (pintype "passive"))
    )
    (net (code "7") (name "/+5V{slash}3V3_16U2") (class "Default")
      (node (ref "C3") (pin "1") (pinfunction "1_1") (pintype "passive"))
      (node (ref "C4") (pin "1") (pinfunction "1_1") (pintype "passive"))
      (node (ref "C5") (pin "1") (pinfunction "1_1") (pintype "passive"))
      (node (ref "FB1") (pin "2") (pinfunction "2_2") (pintype "passive"))
      (node (ref "R26") (pin "2") (pinfunction "2_2") (pintype "passive"))
      (node (ref "U2") (pin "32") (pinfunction "AVCC_32") (pintype "passive"))
      (node (ref "U2") (pin "4") (pinfunction "VCC_4") (pintype "passive"))
    )
    (net (code "8") (name "/+5V{slash}3V3_328P_AVCC") (class "Default")
      (node (ref "C22") (pin "1") (pinfunction "1_1") (pintype "passive"))
      (node (ref "C23") (pin "1") (pinfunction "1_1") (pintype "passive"))
      (node (ref "FB3") (pin "2") (pinfunction "2_2") (pintype "passive"))
      (node (ref "U1") (pin "20") (pinfunction "AVCC_20") (pintype "passive"))
    )
    (net (code "9") (name "/+5V{slash}3V3_328P_VCC") (class "Default")
      (node (ref "C19") (pin "1") (pinfunction "1_1") (pintype "passive"))
      (node (ref "C20") (pin "1") (pinfunction "1_1") (pintype "passive"))
      (node (ref "FB2") (pin "2") (pinfunction "2_2") (pintype "passive"))
      (node (ref "U1") (pin "7") (pinfunction "VCC_7") (pintype "passive"))
    )
    (net (code "10") (name "/16U2PROG_328P_RESETn") (class "Default")
      (node (ref "JP1") (pin "2") (pinfunction "2_2") (pintype "passive"))
      (node (ref "R1") (pin "1") (pinfunction "1_1") (pintype "passive"))
      (node (ref "U2") (pin "13") (pinfunction "~{CTS}_/~{_HWB}_/_T0_/_AIN6_/_INT7_/_PD7_13") (pintype "passive"))
    )
    (net (code "11") (name "/16U2_16MHZ_XTAL1") (class "Default")
      (node (ref "C10") (pin "2") (pinfunction "2_2") (pintype "passive"))
      (node (ref "R9") (pin "1") (pinfunction "1_1") (pintype "passive"))
      (node (ref "U2") (pin "1") (pinfunction "XTAL1_1") (pintype "passive"))
      (node (ref "Y2") (pin "1") (pinfunction "1_1") (pintype "passive"))
    )
    (net (code "12") (name "/16U2_16MHZ_XTAL2") (class "Default")
      (node (ref "C9") (pin "2") (pinfunction "2_2") (pintype "passive"))
      (node (ref "R9") (pin "2") (pinfunction "2_2") (pintype "passive"))
      (node (ref "U2") (pin "2") (pinfunction "XTAL2_/_PC0_2") (pintype "passive"))
      (node (ref "Y2") (pin "2") (pinfunction "2_2") (pintype "passive"))
    )
    (net (code "13") (name "/16U2_BUF_RESETn") (class "Default")
      (node (ref "C31") (pin "1") (pinfunction "1_1") (pintype "passive"))
      (node (ref "R23") (pin "2") (pinfunction "2_2") (pintype "passive"))
      (node (ref "U5") (pin "1") (pinfunction "A_1") (pintype "passive"))
      (node (ref "U5") (pin "2") (pinfunction "B_2") (pintype "passive"))
    )
    (net (code "14") (name "/16U2_HDR_RESETn") (class "Default")
      (node (ref "J6") (pin "5") (pinfunction "5_5") (pintype "passive"))
      (node (ref "JP3") (pin "3") (pinfunction "3_3") (pintype "passive"))
    )
    (net (code "15") (name "/16U2_MISO") (class "Default")
      (node (ref "J6") (pin "1") (pinfunction "1_1") (pintype "passive"))
      (node (ref "U2") (pin "17") (pinfunction "PDO_/_MISO_/_PCINT3_/_PB3_17") (pintype "passive"))
    )
    (net (code "16") (name "/16U2_MOSI") (class "Default")
      (node (ref "J6") (pin "4") (pinfunction "4_4") (pintype "passive"))
      (node (ref "U2") (pin "16") (pinfunction "PDI_/_MOSI_/_PCINT2_/_PB2_16") (pintype "passive"))
    )
    (net (code "17") (name "/16U2_PB4") (class "Default")
      (node (ref "JP2") (pin "1") (pinfunction "1_1") (pintype "passive"))
      (node (ref "JP3") (pin "2") (pinfunction "2_2") (pintype "passive"))
      (node (ref "U2") (pin "18") (pinfunction "T1_/_PCINT4_/_PB4_18") (pintype "passive"))
    )
    (net (code "18") (name "/16U2_PB5") (class "Default")
      (node (ref "JP2") (pin "3") (pinfunction "3_3") (pintype "passive"))
      (node (ref "U2") (pin "19") (pinfunction "PCINT5_/_PB5_19") (pintype "passive"))
    )
    (net (code "19") (name "/16U2_PB6") (class "Default")
      (node (ref "JP2") (pin "2") (pinfunction "2_2") (pintype "passive"))
      (node (ref "U2") (pin "20") (pinfunction "PCINT6_/_PB6_20") (pintype "passive"))
    )
    (net (code "20") (name "/16U2_PB7") (class "Default")
      (node (ref "JP2") (pin "4") (pinfunction "4_4") (pintype "passive"))
      (node (ref "U2") (pin "21") (pinfunction "OC.0A_/_OC.1C_/_PCINT7_/_PB7_21") (pintype "passive"))
    )
    (net (code "21") (name "/16U2_RESETn") (class "Default")
      (node (ref "JP3") (pin "4") (pinfunction "4_4") (pintype "passive"))
      (node (ref "R4") (pin "1") (pinfunction "1_1") (pintype "passive"))
      (node (ref "U2") (pin "24") (pinfunction "PC1_/~{_RESET}_/_DW_24") (pintype "passive"))
      (node (ref "U5") (pin "4") (pinfunction "Y_4") (pintype "passive"))
    )
    (net (code "22") (name "/16U2_RXD") (class "Default")
      (node (ref "R11") (pin "1") (pinfunction "1_1") (pintype "passive"))
      (node (ref "U2") (pin "8") (pinfunction "RXD1_/_AIN1_/_INT2_/_PD2_8") (pintype "passive"))
    )
    (net (code "23") (name "/16U2_RX_LED") (class "Default")
      (node (ref "D4") (pin "1") (pinfunction "cathode_1") (pintype "passive"))
      (node (ref "U2") (pin "10") (pinfunction "AIN3_/_INT5_/_PD4_10") (pintype "passive"))
    )
    (net (code "24") (name "/16U2_SCLK") (class "Default")
      (node (ref "J6") (pin "3") (pinfunction "3_3") (pintype "passive"))
      (node (ref "R5") (pin "2") (pinfunction "2_2") (pintype "passive"))
    )
    (net (code "25") (name "/16U2_SCLK_R") (class "Default")
      (node (ref "R5") (pin "1") (pinfunction "1_1") (pintype "passive"))
      (node (ref "U2") (pin "15") (pinfunction "SCLK_/_PCINT1_/_PB1_15") (pintype "passive"))
    )
    (net (code "26") (name "/16U2_TXD") (class "Default")
      (node (ref "R10") (pin "1") (pinfunction "1_1") (pintype "passive"))
      (node (ref "U2") (pin "9") (pinfunction "TXD1_/_INT3_/_PD3_9") (pintype "passive"))
    )
    (net (code "27") (name "/16U2_TX_LED") (class "Default")
      (node (ref "D3") (pin "1") (pinfunction "cathode_1") (pintype "passive"))
      (node (ref "U2") (pin "11") (pinfunction "XCK_/_AIN4_/_PCINT12_/_PD5_11") (pintype "passive"))
    )
    (net (code "28") (name "/328P_16MHZ_XTAL1") (class "Default")
      (node (ref "C27") (pin "2") (pinfunction "2_2") (pintype "passive"))
      (node (ref "R16") (pin "1") (pinfunction "1_1") (pintype "passive"))
      (node (ref "U1") (pin "9") (pinfunction "PB6_/_PCINT6_/_TOSC1_/_XTAL1_9") (pintype "passive"))
      (node (ref "Y1") (pin "1") (pinfunction "1_1") (pintype "passive"))
    )
    (net (code "29") (name "/328P_16MHZ_XTAL2") (class "Default")
      (node (ref "C25") (pin "2") (pinfunction "2_2") (pintype "passive"))
      (node (ref "R16") (pin "2") (pinfunction "2_2") (pintype "passive"))
      (node (ref "U1") (pin "10") (pinfunction "PB7_/_PCINT7_/_TOSC2_/_XTAL2_10") (pintype "passive"))
      (node (ref "Y1") (pin "2") (pinfunction "2_2") (pintype "passive"))
    )
    (net (code "30") (name "/328P_AUTORESETn") (class "Default")
      (node (ref "C11") (pin "1") (pinfunction "1_1") (pintype "passive"))
      (node (ref "R18") (pin "1") (pinfunction "1_1") (pintype "passive"))
      (node (ref "U6") (pin "1") (pinfunction "A_1") (pintype "passive"))
    )
    (net (code "31") (name "/328P_BUF_RESETn") (class "Default")
      (node (ref "C32") (pin "1") (pinfunction "1_1") (pintype "passive"))
      (node (ref "R24") (pin "2") (pinfunction "2_2") (pintype "passive"))
      (node (ref "U6") (pin "2") (pinfunction "B_2") (pintype "passive"))
    )
    (net (code "32") (name "/328P_RESETn") (class "Default")
      (node (ref "J1") (pin "3") (pinfunction "3_3") (pintype "passive"))
      (node (ref "J5") (pin "5") (pinfunction "5_5") (pintype "passive"))
      (node (ref "JP3") (pin "1") (pinfunction "1_1") (pintype "passive"))
      (node (ref "R14") (pin "1") (pinfunction "1_1") (pintype "passive"))
      (node (ref "U1") (pin "1") (pinfunction "PC6_/_PCINT14_/~{_RESET}_1") (pintype "passive"))
      (node (ref "U6") (pin "4") (pinfunction "Y_4") (pintype "passive"))
    )
    (net (code "33") (name "/AD0") (class "Default")
      (node (ref "J2") (pin "1") (pinfunction "1_1") (pintype "passive"))
      (node (ref "U1") (pin "23") (pinfunction "PCINT8_/_ADC0_/_PC0_23") (pintype "passive"))
    )
    (net (code "34") (name "/AD1") (class "Default")
      (node (ref "J2") (pin "2") (pinfunction "2_2") (pintype "passive"))
      (node (ref "U1") (pin "24") (pinfunction "PCINT9_/_ADC1_/_PC1_24") (pintype "passive"))
    )
    (net (code "35") (name "/AD2") (class "Default")
      (node (ref "J2") (pin "3") (pinfunction "3_3") (pintype "passive"))
      (node (ref "U1") (pin "25") (pinfunction "PCINT10_/_ADC2_/_PC2_25") (pintype "passive"))
    )
    (net (code "36") (name "/AD3") (class "Default")
      (node (ref "J2") (pin "4") (pinfunction "4_4") (pintype "passive"))
      (node (ref "U1") (pin "26") (pinfunction "PCINT11_/_ADC3_/_PC3_26") (pintype "passive"))
    )
    (net (code "37") (name "/AD4{slash}SDA") (class "Default")
      (node (ref "J2") (pin "5") (pinfunction "5_5") (pintype "passive"))
      (node (ref "J4") (pin "9") (pinfunction "9_9") (pintype "passive"))
      (node (ref "U1") (pin "27") (pinfunction "SDA_/_PCINT12_/_ADC4_/_PC4_27") (pintype "passive"))
    )
    (net (code "38") (name "/AD5{slash}SCL") (class "Default")
      (node (ref "J2") (pin "6") (pinfunction "6_6") (pintype "passive"))
      (node (ref "J4") (pin "10") (pinfunction "10_10") (pintype "passive"))
      (node (ref "U1") (pin "28") (pinfunction "SCL_/_PCINT13_/_ADC5_/_PC5_28") (pintype "passive"))
    )
    (net (code "39") (name "/BUTTON_RESETn") (class "Default")
      (node (ref "D6") (pin "2") (pinfunction "Anode_2") (pintype "passive"))
      (node (ref "R20") (pin "1") (pinfunction "1_1") (pintype "passive"))
      (node (ref "R24") (pin "1") (pinfunction "1_1") (pintype "passive"))
      (node (ref "SW1") (pin "1") (pinfunction "1_1") (pintype "passive"))
      (node (ref "SW1") (pin "2") (pinfunction "2_2") (pintype "passive"))
    )
    (net (code "40") (name "/CON_USB_N") (class "Default")
      (node (ref "J7") (pin "2") (pinfunction "P2_2") (pintype "passive"))
      (node (ref "R6") (pin "1") (pinfunction "1_1") (pintype "passive"))
      (node (ref "Z1") (pin "2") (pinfunction "2_2") (pintype "passive"))
    )
    (net (code "41") (name "/CON_USB_P") (class "Default")
      (node (ref "J7") (pin "3") (pinfunction "P3_3") (pintype "passive"))
      (node (ref "R7") (pin "1") (pinfunction "1_1") (pintype "passive"))
      (node (ref "Z2") (pin "2") (pinfunction "2_2") (pintype "passive"))
    )
    (net (code "42") (name "/IO0") (class "Default")
      (node (ref "J3") (pin "1") (pinfunction "1_1") (pintype "passive"))
      (node (ref "R10") (pin "2") (pinfunction "2_2") (pintype "passive"))
      (node (ref "U1") (pin "2") (pinfunction "RXD_/_PCINT16_/_PD0_2") (pintype "passive"))
    )
    (net (code "43") (name "/IO1") (class "Default")
      (node (ref "J3") (pin "2") (pinfunction "2_2") (pintype "passive"))
      (node (ref "R11") (pin "2") (pinfunction "2_2") (pintype "passive"))
      (node (ref "U1") (pin "3") (pinfunction "TXD_/_PCINT17_/_PD1_3") (pintype "passive"))
    )
    (net (code "44") (name "/IO2") (class "Default")
      (node (ref "J3") (pin "3") (pinfunction "3_3") (pintype "passive"))
      (node (ref "U1") (pin "4") (pinfunction "INT0_/_PCINT18_/_PD2_4") (pintype "passive"))
    )
    (net (code "45") (name "/IO3") (class "Default")
      (node (ref "J3") (pin "4") (pinfunction "4_4") (pintype "passive"))
      (node (ref "U1") (pin "5") (pinfunction "OC2B_/_INT1_/_PCINT19_/_PD3_5") (pintype "passive"))
    )
    (net (code "46") (name "/IO4") (class "Default")
      (node (ref "J3") (pin "5") (pinfunction "5_5") (pintype "passive"))
      (node (ref "U1") (pin "6") (pinfunction "XCK_/_T0_/_PCINT20_/_PD4_6") (pintype "passive"))
    )
    (net (code "47") (name "/IO5") (class "Default")
      (node (ref "J3") (pin "6") (pinfunction "6_6") (pintype "passive"))
      (node (ref "U1") (pin "11") (pinfunction "OC0B_/_T1_/_PCINT21_/_PD5_11") (pintype "passive"))
    )
    (net (code "48") (name "/IO6") (class "Default")
      (node (ref "J3") (pin "7") (pinfunction "7_7") (pintype "passive"))
      (node (ref "U1") (pin "12") (pinfunction "OC0A_/_AIN0_/_PCINT22_/_PD6_12") (pintype "passive"))
    )
    (net (code "49") (name "/IO7") (class "Default")
      (node (ref "J3") (pin "8") (pinfunction "8_8") (pintype "passive"))
      (node (ref "U1") (pin "13") (pinfunction "AIN1_/_PCINT23_/_PD7_13") (pintype "passive"))
    )
    (net (code "50") (name "/IO8") (class "Default")
      (node (ref "J4") (pin "1") (pinfunction "1_1") (pintype "passive"))
      (node (ref "R22") (pin "1") (pinfunction "1_1") (pintype "passive"))
      (node (ref "U1") (pin "14") (pinfunction "CLKO_/_ICP1_/_PCINT0_/_PB0_14") (pintype "passive"))
    )
    (net (code "51") (name "/IO9") (class "Default")
      (node (ref "J4") (pin "2") (pinfunction "2_2") (pintype "passive"))
      (node (ref "U1") (pin "15") (pinfunction "OC1A_/_PCINT1_/_PB1_15") (pintype "passive"))
    )
    (net (code "52") (name "/MISO") (class "Default")
      (node (ref "J4") (pin "5") (pinfunction "5_5") (pintype "passive"))
      (node (ref "J5") (pin "1") (pinfunction "1_1") (pintype "passive"))
      (node (ref "U1") (pin "18") (pinfunction "MISO_/_PCINT4_/_PB4_18") (pintype "passive"))
    )
    (net (code "53") (name "/MOSI") (class "Default")
      (node (ref "J4") (pin "4") (pinfunction "4_4") (pintype "passive"))
      (node (ref "J5") (pin "4") (pinfunction "4_4") (pintype "passive"))
      (node (ref "U1") (pin "17") (pinfunction "MOSI_/_OC2A_/_PCINT3_/_PB3_17") (pintype "passive"))
    )
    (net (code "54") (name "/SCK") (class "Default")
      (node (ref "J4") (pin "6") (pinfunction "6_6") (pintype "passive"))
      (node (ref "J5") (pin "3") (pinfunction "3_3") (pintype "passive"))
      (node (ref "R13") (pin "2") (pinfunction "2_2") (pintype "passive"))
      (node (ref "U4") (pin "1") (pinfunction "A_1") (pintype "passive"))
      (node (ref "U4") (pin "2") (pinfunction "B_2") (pintype "passive"))
    )
    (net (code "55") (name "/SCK_R") (class "Default")
      (node (ref "R13") (pin "1") (pinfunction "1_1") (pintype "passive"))
      (node (ref "U1") (pin "19") (pinfunction "SCK_/_PCINT5_/_PB5_19") (pintype "passive"))
    )
    (net (code "56") (name "/SS") (class "Default")
      (node (ref "J4") (pin "3") (pinfunction "3_3") (pintype "passive"))
      (node (ref "U1") (pin "16") (pinfunction "~{SS}_/_OC1B_/_PCINT2_/_PB2_16") (pintype "passive"))
    )
    (net (code "57") (name "/USB_N") (class "Default")
      (node (ref "R6") (pin "2") (pinfunction "2_2") (pintype "passive"))
      (node (ref "U2") (pin "30") (pinfunction "D-_30") (pintype "passive"))
    )
    (net (code "58") (name "/USB_P") (class "Default")
      (node (ref "R7") (pin "2") (pinfunction "2_2") (pintype "passive"))
      (node (ref "U2") (pin "29") (pinfunction "D+_29") (pintype "passive"))
    )
    (net (code "59") (name "/USER_BUTTON") (class "Default")
      (node (ref "R21") (pin "1") (pinfunction "1_1") (pintype "passive"))
      (node (ref "R25") (pin "1") (pinfunction "1_1") (pintype "passive"))
      (node (ref "SW2") (pin "1") (pinfunction "1_1") (pintype "passive"))
      (node (ref "SW2") (pin "2") (pinfunction "2_2") (pintype "passive"))
    )
    (net (code "60") (name "/USER_BUTTON_BUF") (class "Default")
      (node (ref "C33") (pin "1") (pinfunction "1_1") (pintype "passive"))
      (node (ref "R25") (pin "2") (pinfunction "2_2") (pintype "passive"))
      (node (ref "U7") (pin "1") (pinfunction "A_1") (pintype "passive"))
      (node (ref "U7") (pin "2") (pinfunction "B_2") (pintype "passive"))
    )
    (net (code "61") (name "GND") (class "Default")
      (node (ref "C1") (pin "2") (pinfunction "2_2") (pintype "passive"))
      (node (ref "C10") (pin "1") (pinfunction "1_1") (pintype "passive"))
      (node (ref "C12") (pin "2") (pinfunction "2_2") (pintype "passive"))
      (node (ref "C13") (pin "2") (pinfunction "2_2") (pintype "passive"))
      (node (ref "C14") (pin "2") (pinfunction "2_2") (pintype "passive"))
      (node (ref "C15") (pin "2") (pinfunction "2_2") (pintype "passive"))
      (node (ref "C16") (pin "2") (pinfunction "2_2") (pintype "passive"))
      (node (ref "C17") (pin "2") (pinfunction "2_2") (pintype "passive"))
      (node (ref "C19") (pin "2") (pinfunction "2_2") (pintype "passive"))
      (node (ref "C2") (pin "2") (pinfunction "2_2") (pintype "passive"))
      (node (ref "C20") (pin "2") (pinfunction "2_2") (pintype "passive"))
      (node (ref "C21") (pin "2") (pinfunction "2_2") (pintype "passive"))
      (node (ref "C22") (pin "2") (pinfunction "2_2") (pintype "passive"))
      (node (ref "C23") (pin "2") (pinfunction "2_2") (pintype "passive"))
      (node (ref "C24") (pin "2") (pinfunction "2_2") (pintype "passive"))
      (node (ref "C25") (pin "1") (pinfunction "1_1") (pintype "passive"))
      (node (ref "C26") (pin "2") (pinfunction "2_2") (pintype "passive"))
      (node (ref "C27") (pin "1") (pinfunction "1_1") (pintype "passive"))
      (node (ref "C28") (pin "2") (pinfunction "2_2") (pintype "passive"))
      (node (ref "C29") (pin "2") (pinfunction "2_2") (pintype "passive"))
      (node (ref "C3") (pin "2") (pinfunction "2_2") (pintype "passive"))
      (node (ref "C30") (pin "2") (pinfunction "2_2") (pintype "passive"))
      (node (ref "C31") (pin "2") (pinfunction "2_2") (pintype "passive"))
      (node (ref "C32") (pin "2") (pinfunction "2_2") (pintype "passive"))
      (node (ref "C33") (pin "2") (pinfunction "2_2") (pintype "passive"))
      (node (ref "C34") (pin "2") (pinfunction "2_2") (pintype "passive"))
      (node (ref "C4") (pin "2") (pinfunction "2_2") (pintype "passive"))
      (node (ref "C5") (pin "2") (pinfunction "2_2") (pintype "passive"))
      (node (ref "C6") (pin "2") (pinfunction "2_2") (pintype "passive"))
      (node (ref "C7") (pin "1") (pinfunction "1_1") (pintype "passive"))
      (node (ref "C8") (pin "2") (pinfunction "2_2") (pintype "passive"))
      (node (ref "C9") (pin "1") (pinfunction "1_1") (pintype "passive"))
      (node (ref "D1") (pin "1") (pinfunction "cathode_1") (pintype "passive"))
      (node (ref "J1") (pin "6") (pinfunction "6_6") (pintype "passive"))
      (node (ref "J1") (pin "7") (pinfunction "7_7") (pintype "passive"))
      (node (ref "J4") (pin "7") (pinfunction "7_7") (pintype "passive"))
      (node (ref "J5") (pin "6") (pinfunction "6_6") (pintype "passive"))
      (node (ref "J6") (pin "6") (pinfunction "6_6") (pintype "passive"))
      (node (ref "J7") (pin "10") (pinfunction "10_10") (pintype "passive"))
      (node (ref "J7") (pin "11") (pinfunction "11_11") (pintype "passive"))
      (node (ref "J7") (pin "5") (pinfunction "P5_5") (pintype "passive"))
      (node (ref "J7") (pin "6") (pinfunction "6_6") (pintype "passive"))
      (node (ref "J7") (pin "7") (pinfunction "7_7") (pintype "passive"))
      (node (ref "J7") (pin "8") (pinfunction "8_8") (pintype "passive"))
      (node (ref "J7") (pin "9") (pinfunction "9_9") (pintype "passive"))
      (node (ref "J9") (pin "1") (pinfunction "1_1") (pintype "passive"))
      (node (ref "MH1") (pin "1") (pinfunction "1_1") (pintype "passive"))
      (node (ref "MH2") (pin "1") (pinfunction "1_1") (pintype "passive"))
      (node (ref "MH3") (pin "1") (pinfunction "1_1") (pintype "passive"))
      (node (ref "R12") (pin "2") (pinfunction "2_2") (pintype "passive"))
      (node (ref "R8") (pin "2") (pinfunction "2_2") (pintype "passive"))
      (node (ref "SW1") (pin "3") (pinfunction "MECH1_3") (pintype "passive"))
      (node (ref "SW1") (pin "4") (pinfunction "MECH2_4") (pintype "passive"))
      (node (ref "SW2") (pin "3") (pinfunction "MECH1_3") (pintype "passive"))
      (node (ref "SW2") (pin "4") (pinfunction "MECH2_4") (pintype "passive"))
      (node (ref "U1") (pin "22") (pinfunction "GND_2_22") (pintype "passive"))
      (node (ref "U1") (pin "8") (pinfunction "GND_1_8") (pintype "passive"))
      (node (ref "U2") (pin "28") (pinfunction "UGND_28") (pintype "passive"))
      (node (ref "U2") (pin "3") (pinfunction "GND_3") (pintype "passive"))
      (node (ref "U3") (pin "3") (pinfunction "GND_3") (pintype "passive"))
      (node (ref "U3") (pin "6") (pinfunction "EPAD_6") (pintype "passive"))
      (node (ref "U4") (pin "3") (pinfunction "GND_3") (pintype "power_in"))
      (node (ref "U5") (pin "3") (pinfunction "GND_3") (pintype "power_in"))
      (node (ref "U6") (pin "3") (pinfunction "GND_3") (pintype "power_in"))
      (node (ref "U7") (pin "3") (pinfunction "GND_3") (pintype "power_in"))
      (node (ref "Z1") (pin "1") (pinfunction "1_1") (pintype "passive"))
      (node (ref "Z2") (pin "1") (pinfunction "1_1") (pintype "passive"))
    )
    (net (code "62") (name "Net-(C11-Pad2)") (class "Default")
      (node (ref "C11") (pin "2") (pinfunction "2_2") (pintype "passive"))
      (node (ref "JP1") (pin "1") (pinfunction "1_1") (pintype "passive"))
    )
    (net (code "63") (name "Net-(D1-ANODE)") (class "Default")
      (node (ref "D1") (pin "2") (pinfunction "ANODE_2") (pintype "passive"))
      (node (ref "R17") (pin "1") (pinfunction "1_1") (pintype "passive"))
    )
    (net (code "64") (name "Net-(D2-ANODE)") (class "Default")
      (node (ref "D2") (pin "2") (pinfunction "ANODE_2") (pintype "passive"))
      (node (ref "R15") (pin "1") (pinfunction "1_1") (pintype "passive"))
    )
    (net (code "65") (name "Net-(D2-cathode)") (class "Default")
      (node (ref "D2") (pin "1") (pinfunction "cathode_1") (pintype "passive"))
      (node (ref "U4") (pin "4") (pinfunction "Y_4") (pintype "passive"))
    )
    (net (code "66") (name "Net-(D3-ANODE)") (class "Default")
      (node (ref "D3") (pin "2") (pinfunction "ANODE_2") (pintype "passive"))
      (node (ref "R2") (pin "1") (pinfunction "1_1") (pintype "passive"))
    )
    (net (code "67") (name "Net-(D4-ANODE)") (class "Default")
      (node (ref "D4") (pin "2") (pinfunction "ANODE_2") (pintype "passive"))
      (node (ref "R3") (pin "1") (pinfunction "1_1") (pintype "passive"))
    )
    (net (code "68") (name "Net-(D5-Anode)") (class "Default")
      (node (ref "D5") (pin "2") (pinfunction "Anode_2") (pintype "passive"))
      (node (ref "R19") (pin "1") (pinfunction "1_1") (pintype "passive"))
      (node (ref "R23") (pin "1") (pinfunction "1_1") (pintype "passive"))
    )
    (net (code "69") (name "Net-(J7-P4)") (class "Default")
      (node (ref "J7") (pin "4") (pinfunction "P4_4") (pintype "passive"))
      (node (ref "R8") (pin "1") (pinfunction "1_1") (pintype "passive"))
    )
    (net (code "70") (name "Net-(JP1-Pad3)") (class "Default")
      (node (ref "JP1") (pin "3") (pinfunction "3_3") (pintype "passive"))
      (node (ref "R12") (pin "1") (pinfunction "1_1") (pintype "passive"))
    )
    (net (code "71") (name "Net-(U7-Y)") (class "Default")
      (node (ref "R22") (pin "2") (pinfunction "2_2") (pintype "passive"))
      (node (ref "U7") (pin "4") (pinfunction "Y_4") (pintype "passive"))
    )
    (net (code "72") (name "unconnected-(J1-Pad1)") (class "Default")
      (node (ref "J1") (pin "1") (pinfunction "1_1") (pintype "passive+no_connect"))
    )
    (net (code "73") (name "unconnected-(J1-Pad8)") (class "Default")
      (node (ref "J1") (pin "8") (pinfunction "8_8") (pintype "passive+no_connect"))
    )
    (net (code "74") (name "unconnected-(MH4-Pad1)") (class "Default")
      (node (ref "MH4") (pin "1") (pinfunction "1_1") (pintype "passive+no_connect"))
    )
    (net (code "75") (name "unconnected-(U2-AIN0_{slash}_INT1_{slash}_PD1-Pad7)") (class "Default")
      (node (ref "U2") (pin "7") (pinfunction "AIN0_/_INT1_/_PD1_7") (pintype "passive+no_connect"))
    )
    (net (code "76") (name "unconnected-(U2-AIN2_{slash}_PCINT11_{slash}_PC2-Pad5)") (class "Default")
      (node (ref "U2") (pin "5") (pinfunction "AIN2_/_PCINT11_/_PC2_5") (pintype "passive+no_connect"))
    )
    (net (code "77") (name "unconnected-(U2-CLKO_{slash}_ICP1_{slash}_INT4_{slash}_PC7-Pad22)") (class "Default")
      (node (ref "U2") (pin "22") (pinfunction "CLKO_/_ICP1_/_INT4_/_PC7_22") (pintype "passive+no_connect"))
    )
    (net (code "78") (name "unconnected-(U2-OC.0B_{slash}_INT0_{slash}_PD0-Pad6)") (class "Default")
      (node (ref "U2") (pin "6") (pinfunction "OC.0B_/_INT0_/_PD0_6") (pintype "passive+no_connect"))
    )
    (net (code "79") (name "unconnected-(U2-OC.1A_{slash}_PCINT8_{slash}_PC6-Pad23)") (class "Default")
      (node (ref "U2") (pin "23") (pinfunction "OC.1A_/_PCINT8_/_PC6_23") (pintype "passive+no_connect"))
    )
    (net (code "80") (name "unconnected-(U2-OC.1B_{slash}_PCINT9_{slash}_PC5-Pad25)") (class "Default")
      (node (ref "U2") (pin "25") (pinfunction "OC.1B_/_PCINT9_/_PC5_25") (pintype "passive+no_connect"))
    )
    (net (code "81") (name "unconnected-(U2-PCINT10_{slash}_PC4-Pad26)") (class "Default")
      (node (ref "U2") (pin "26") (pinfunction "PCINT10_/_PC4_26") (pintype "passive+no_connect"))
    )
    (net (code "82") (name "unconnected-(U2-~{RTS}_{slash}_AIN5_{slash}_INT6_{slash}_PD6-Pad12)") (class "Default")
      (node (ref "U2") (pin "12") (pinfunction "~{RTS}_/_AIN5_/_INT6_/_PD6_12") (pintype "passive"))
    )
    (net (code "83") (name "unconnected-(U2-~{SS}_{slash}_PCINT0_{slash}_PB0-Pad14)") (class "Default")
      (node (ref "U2") (pin "14") (pinfunction "~{SS}_/_PCINT0_/_PB0_14") (pintype "passive+no_connect"))
    )
  )
)
